# ReducedModel.net
KiCad netlist of a schematic drawn in EAGLE
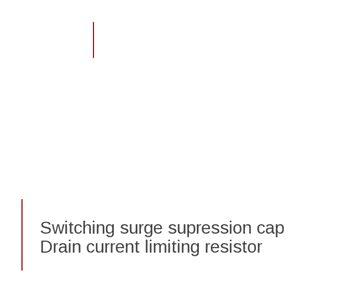
[diagram p0: schematic, sheet 3, part 1 of 2]
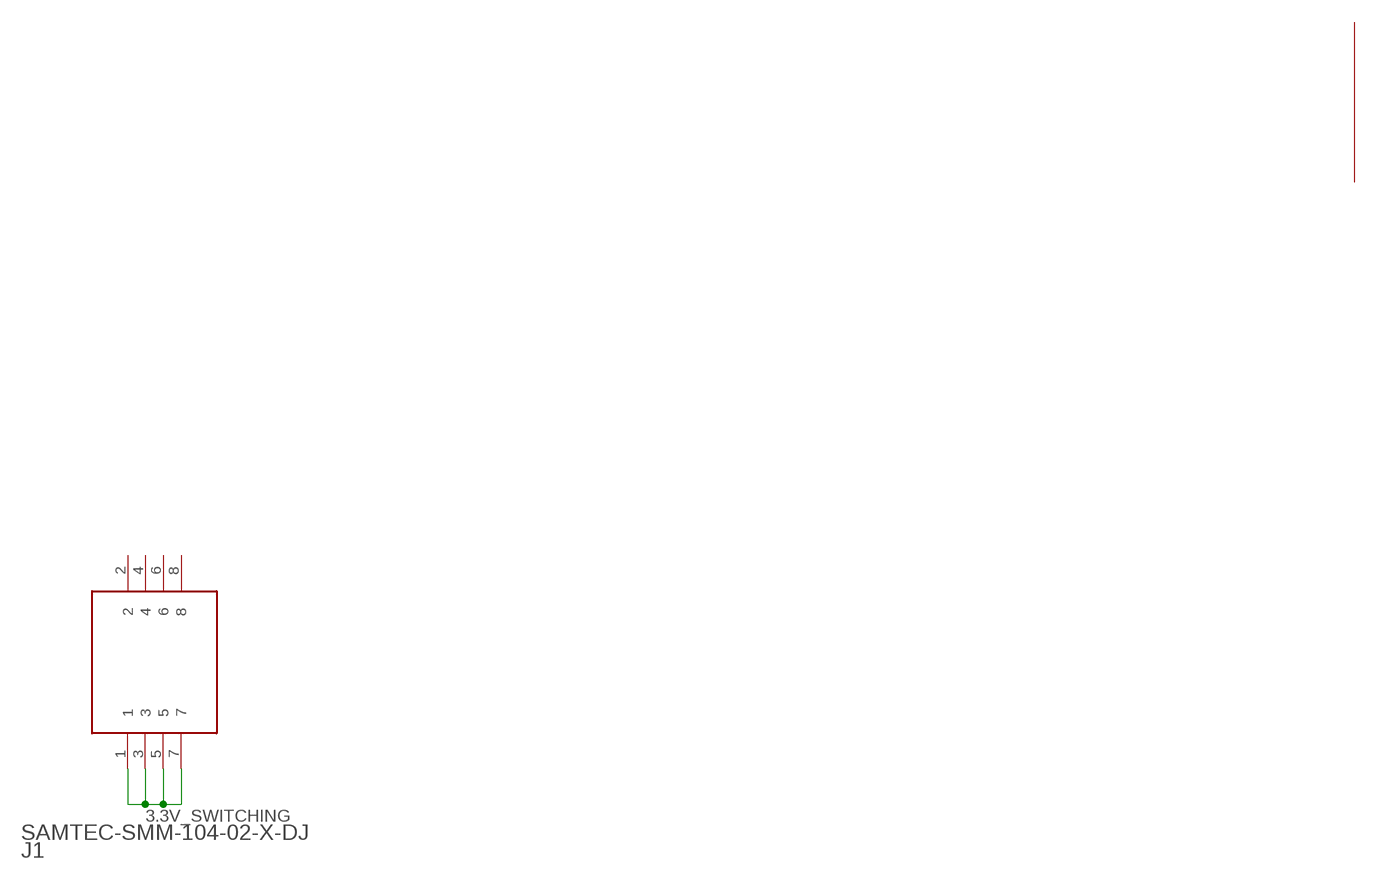
[diagram p1: schematic, sheet 3, part 2 of 2]
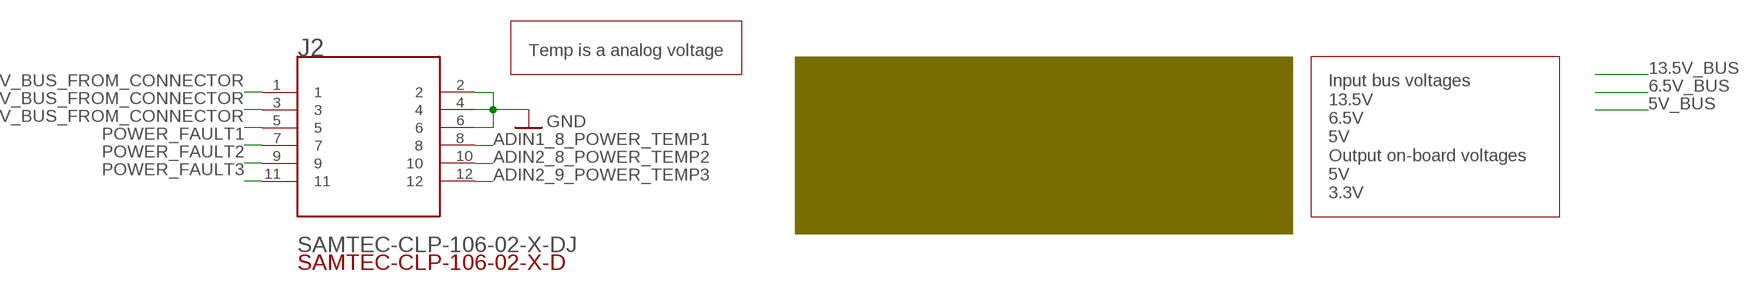
[diagram p2: schematic, sheet 4]
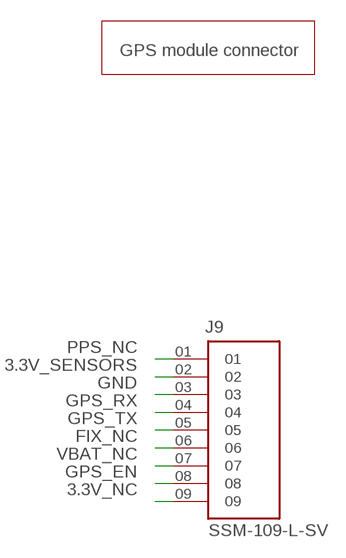
[diagram p3: schematic, sheet 7]
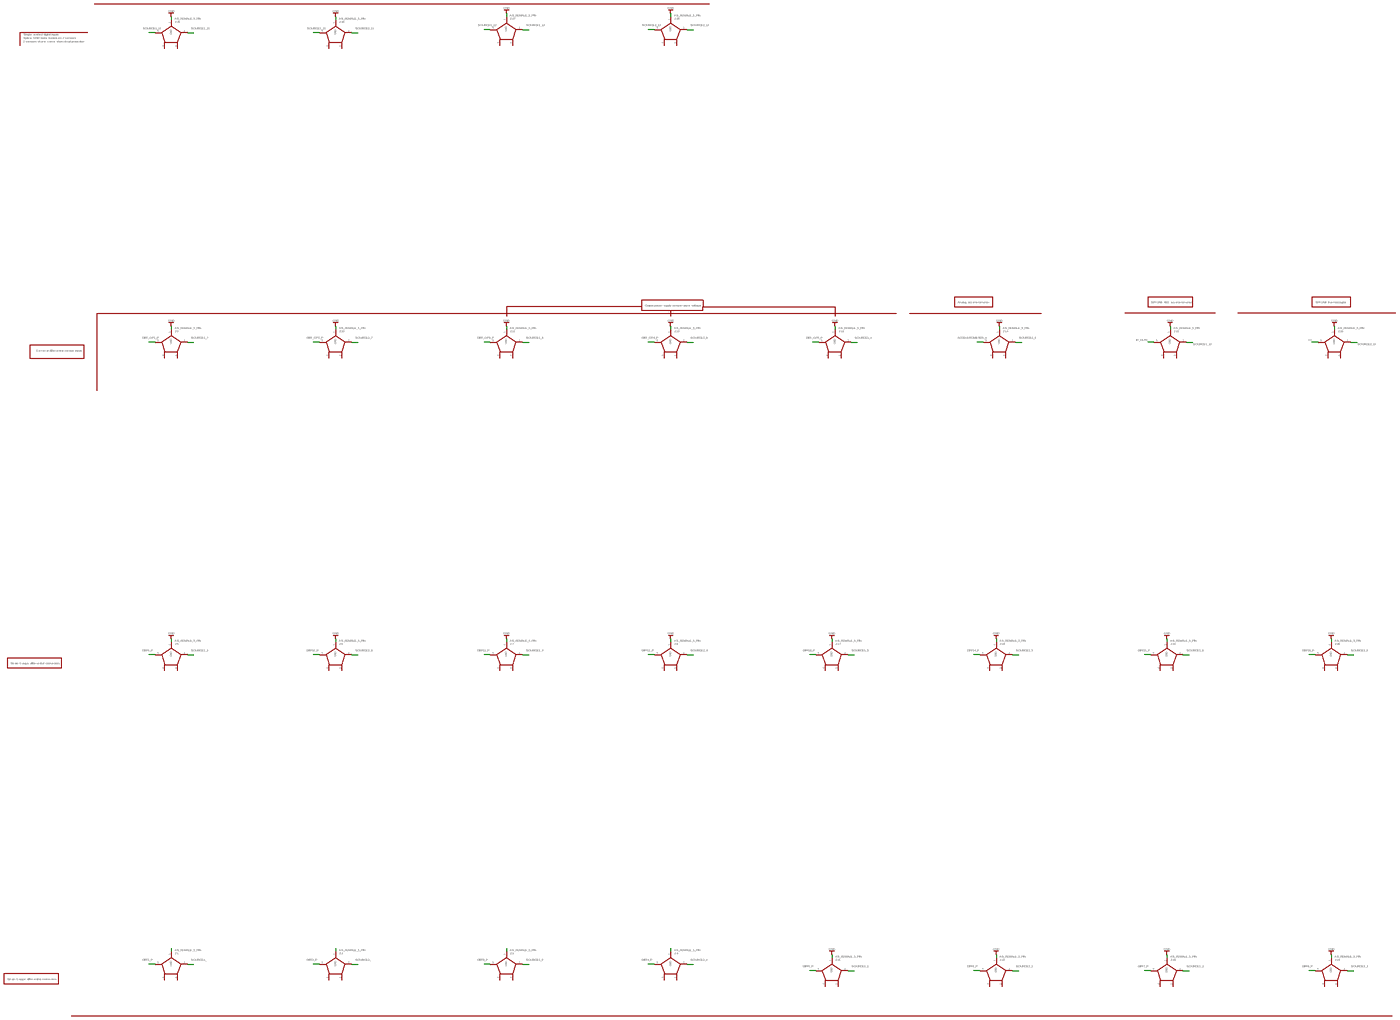
[diagram p4: schematic, sheet 11, overview]
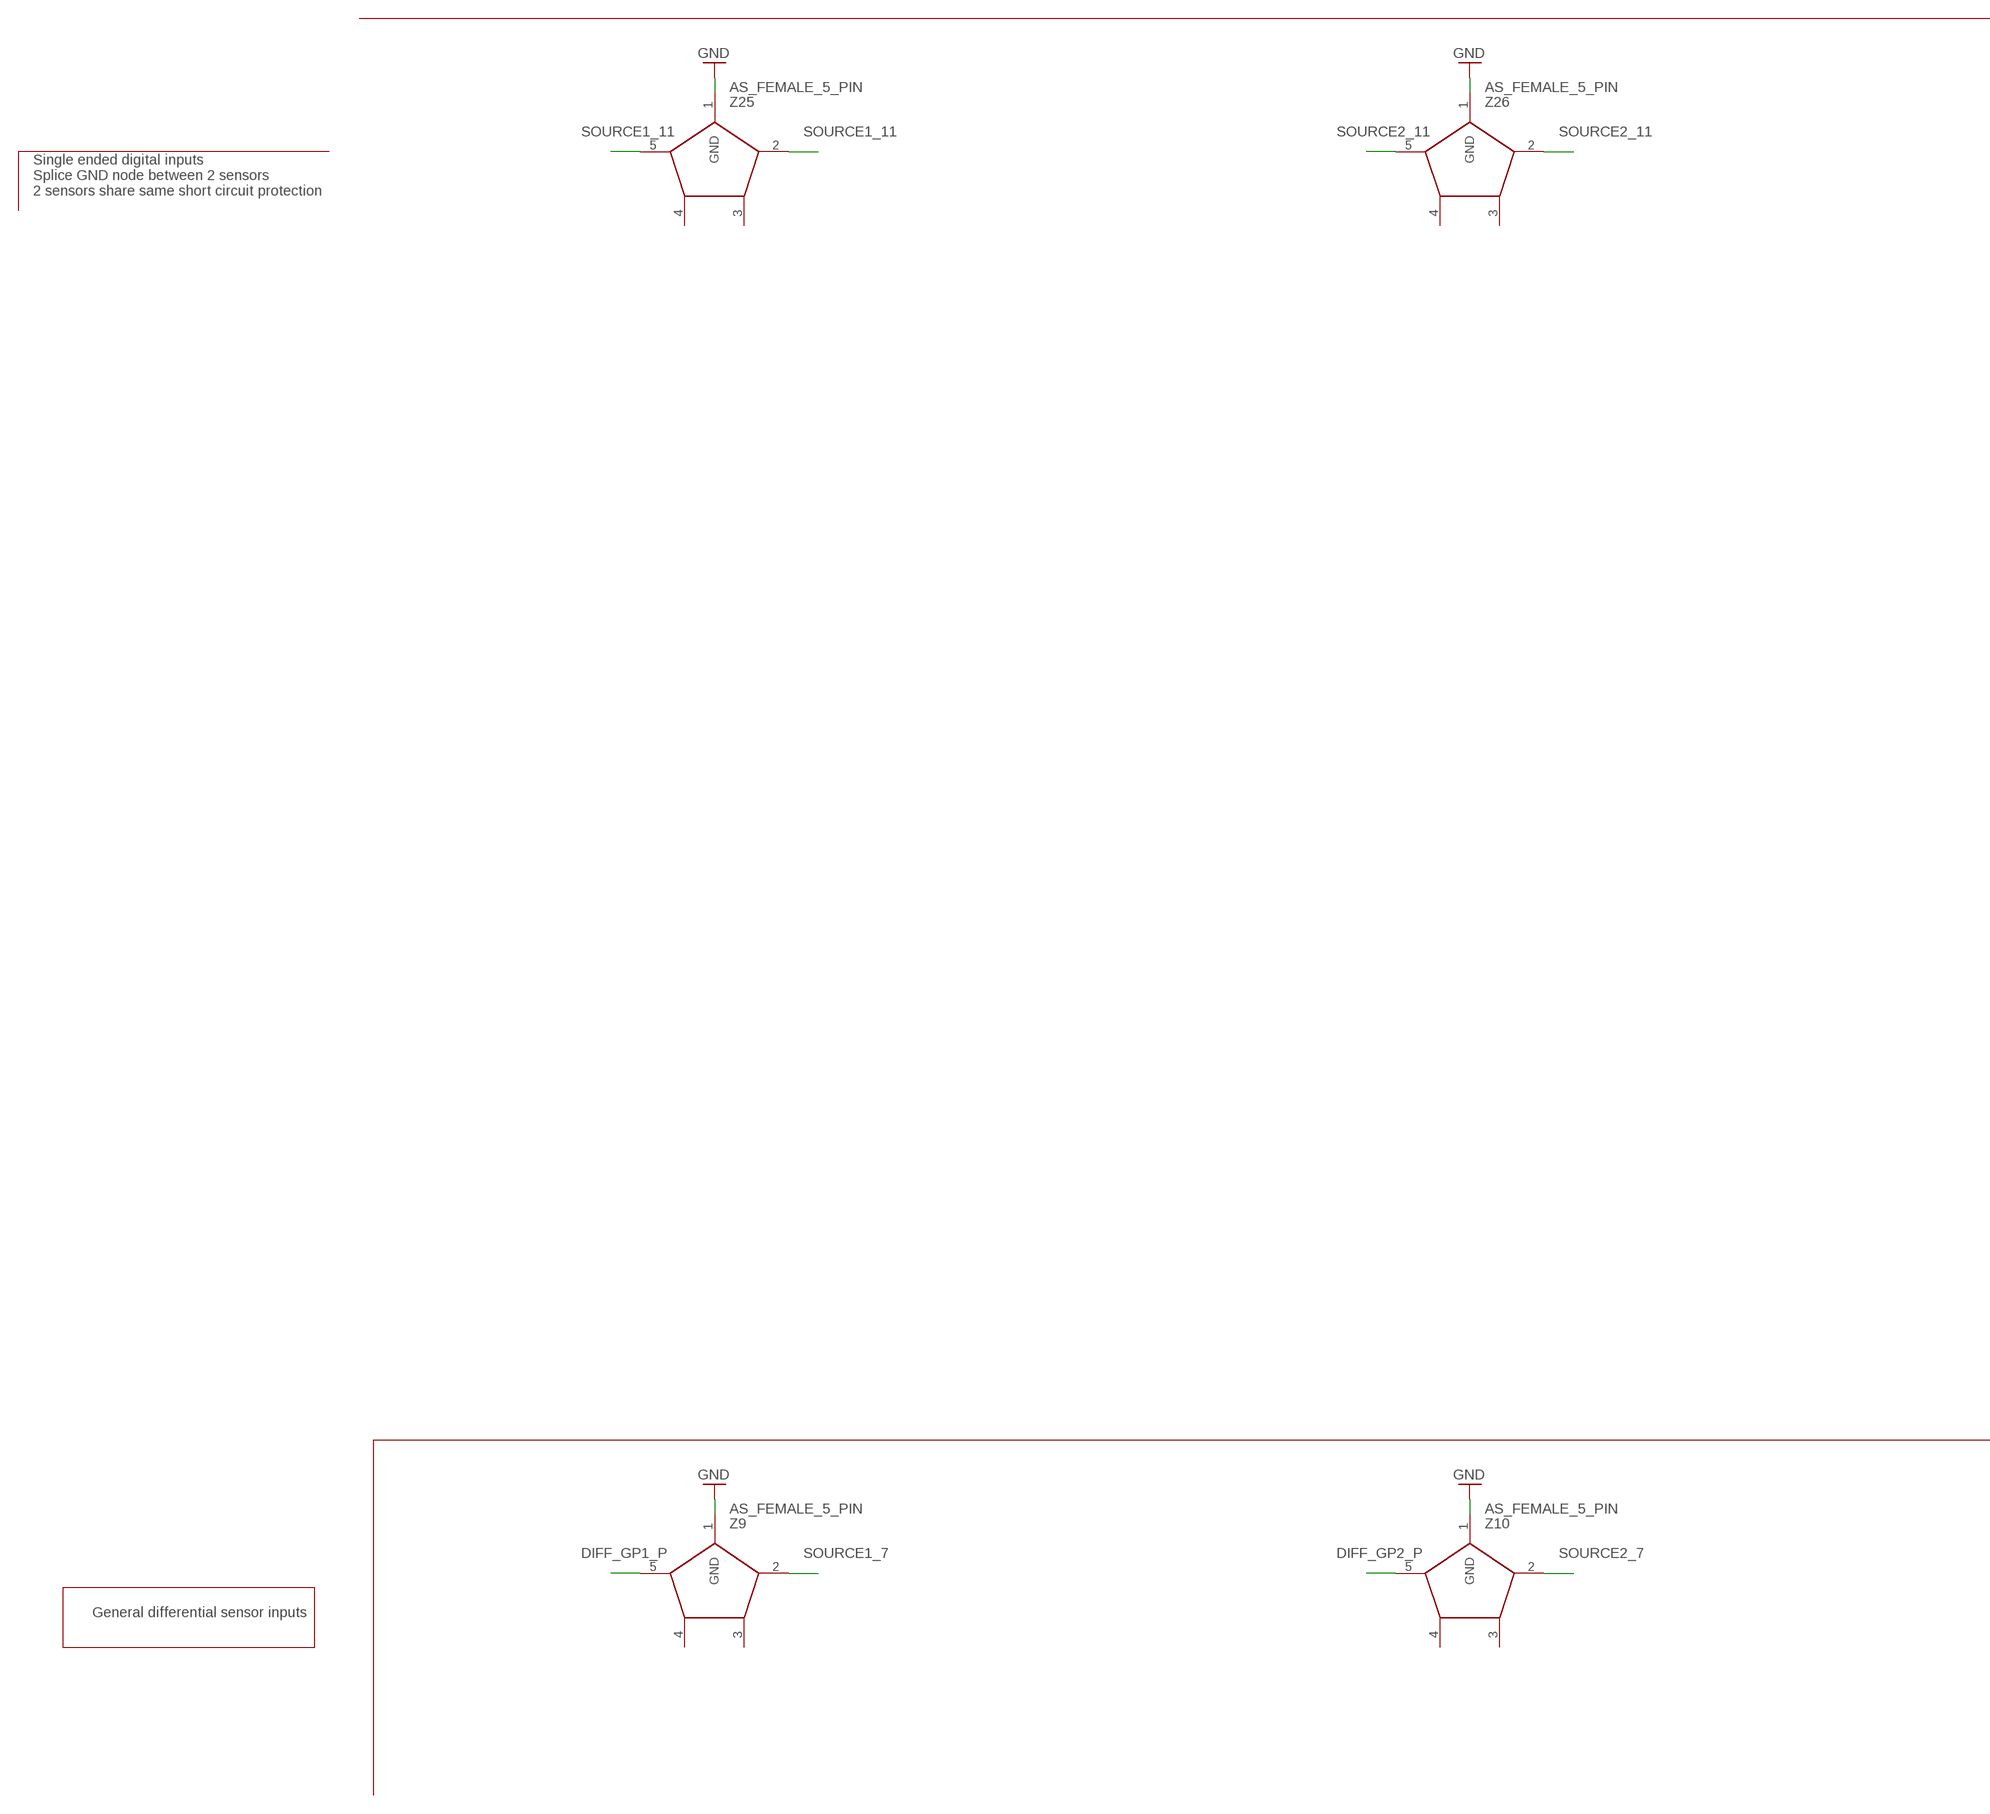
[diagram p5: schematic, sheet 11, part 1 of 6]
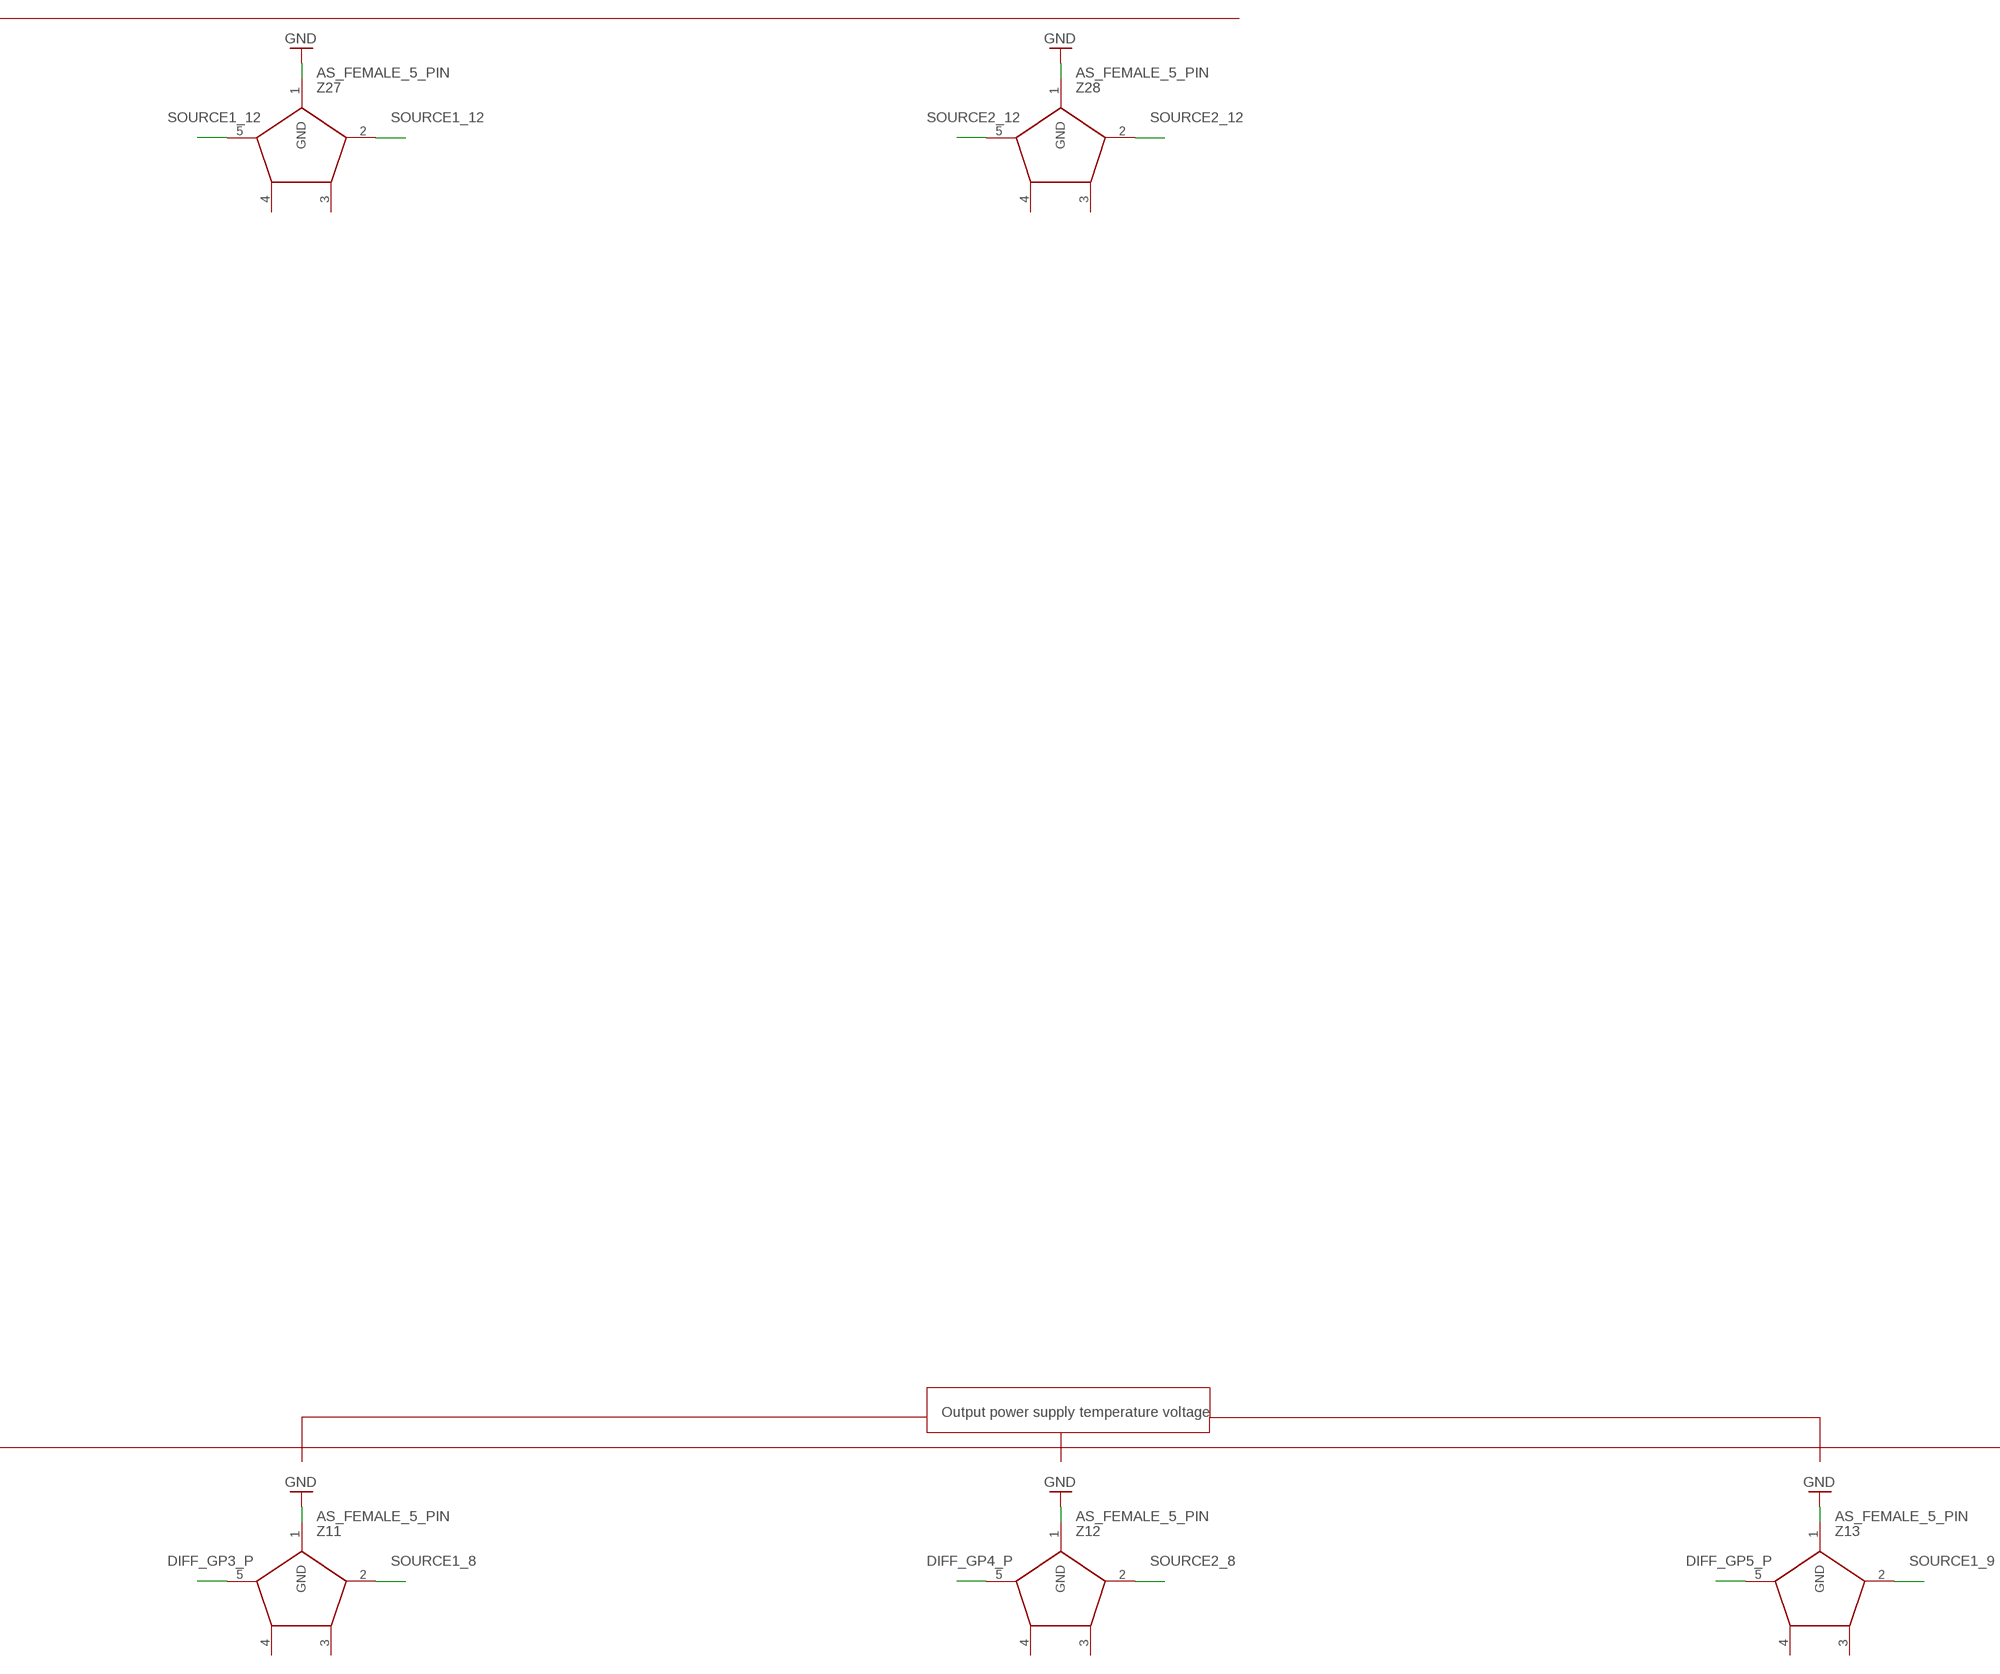
[diagram p6: schematic, sheet 11, part 2 of 6]
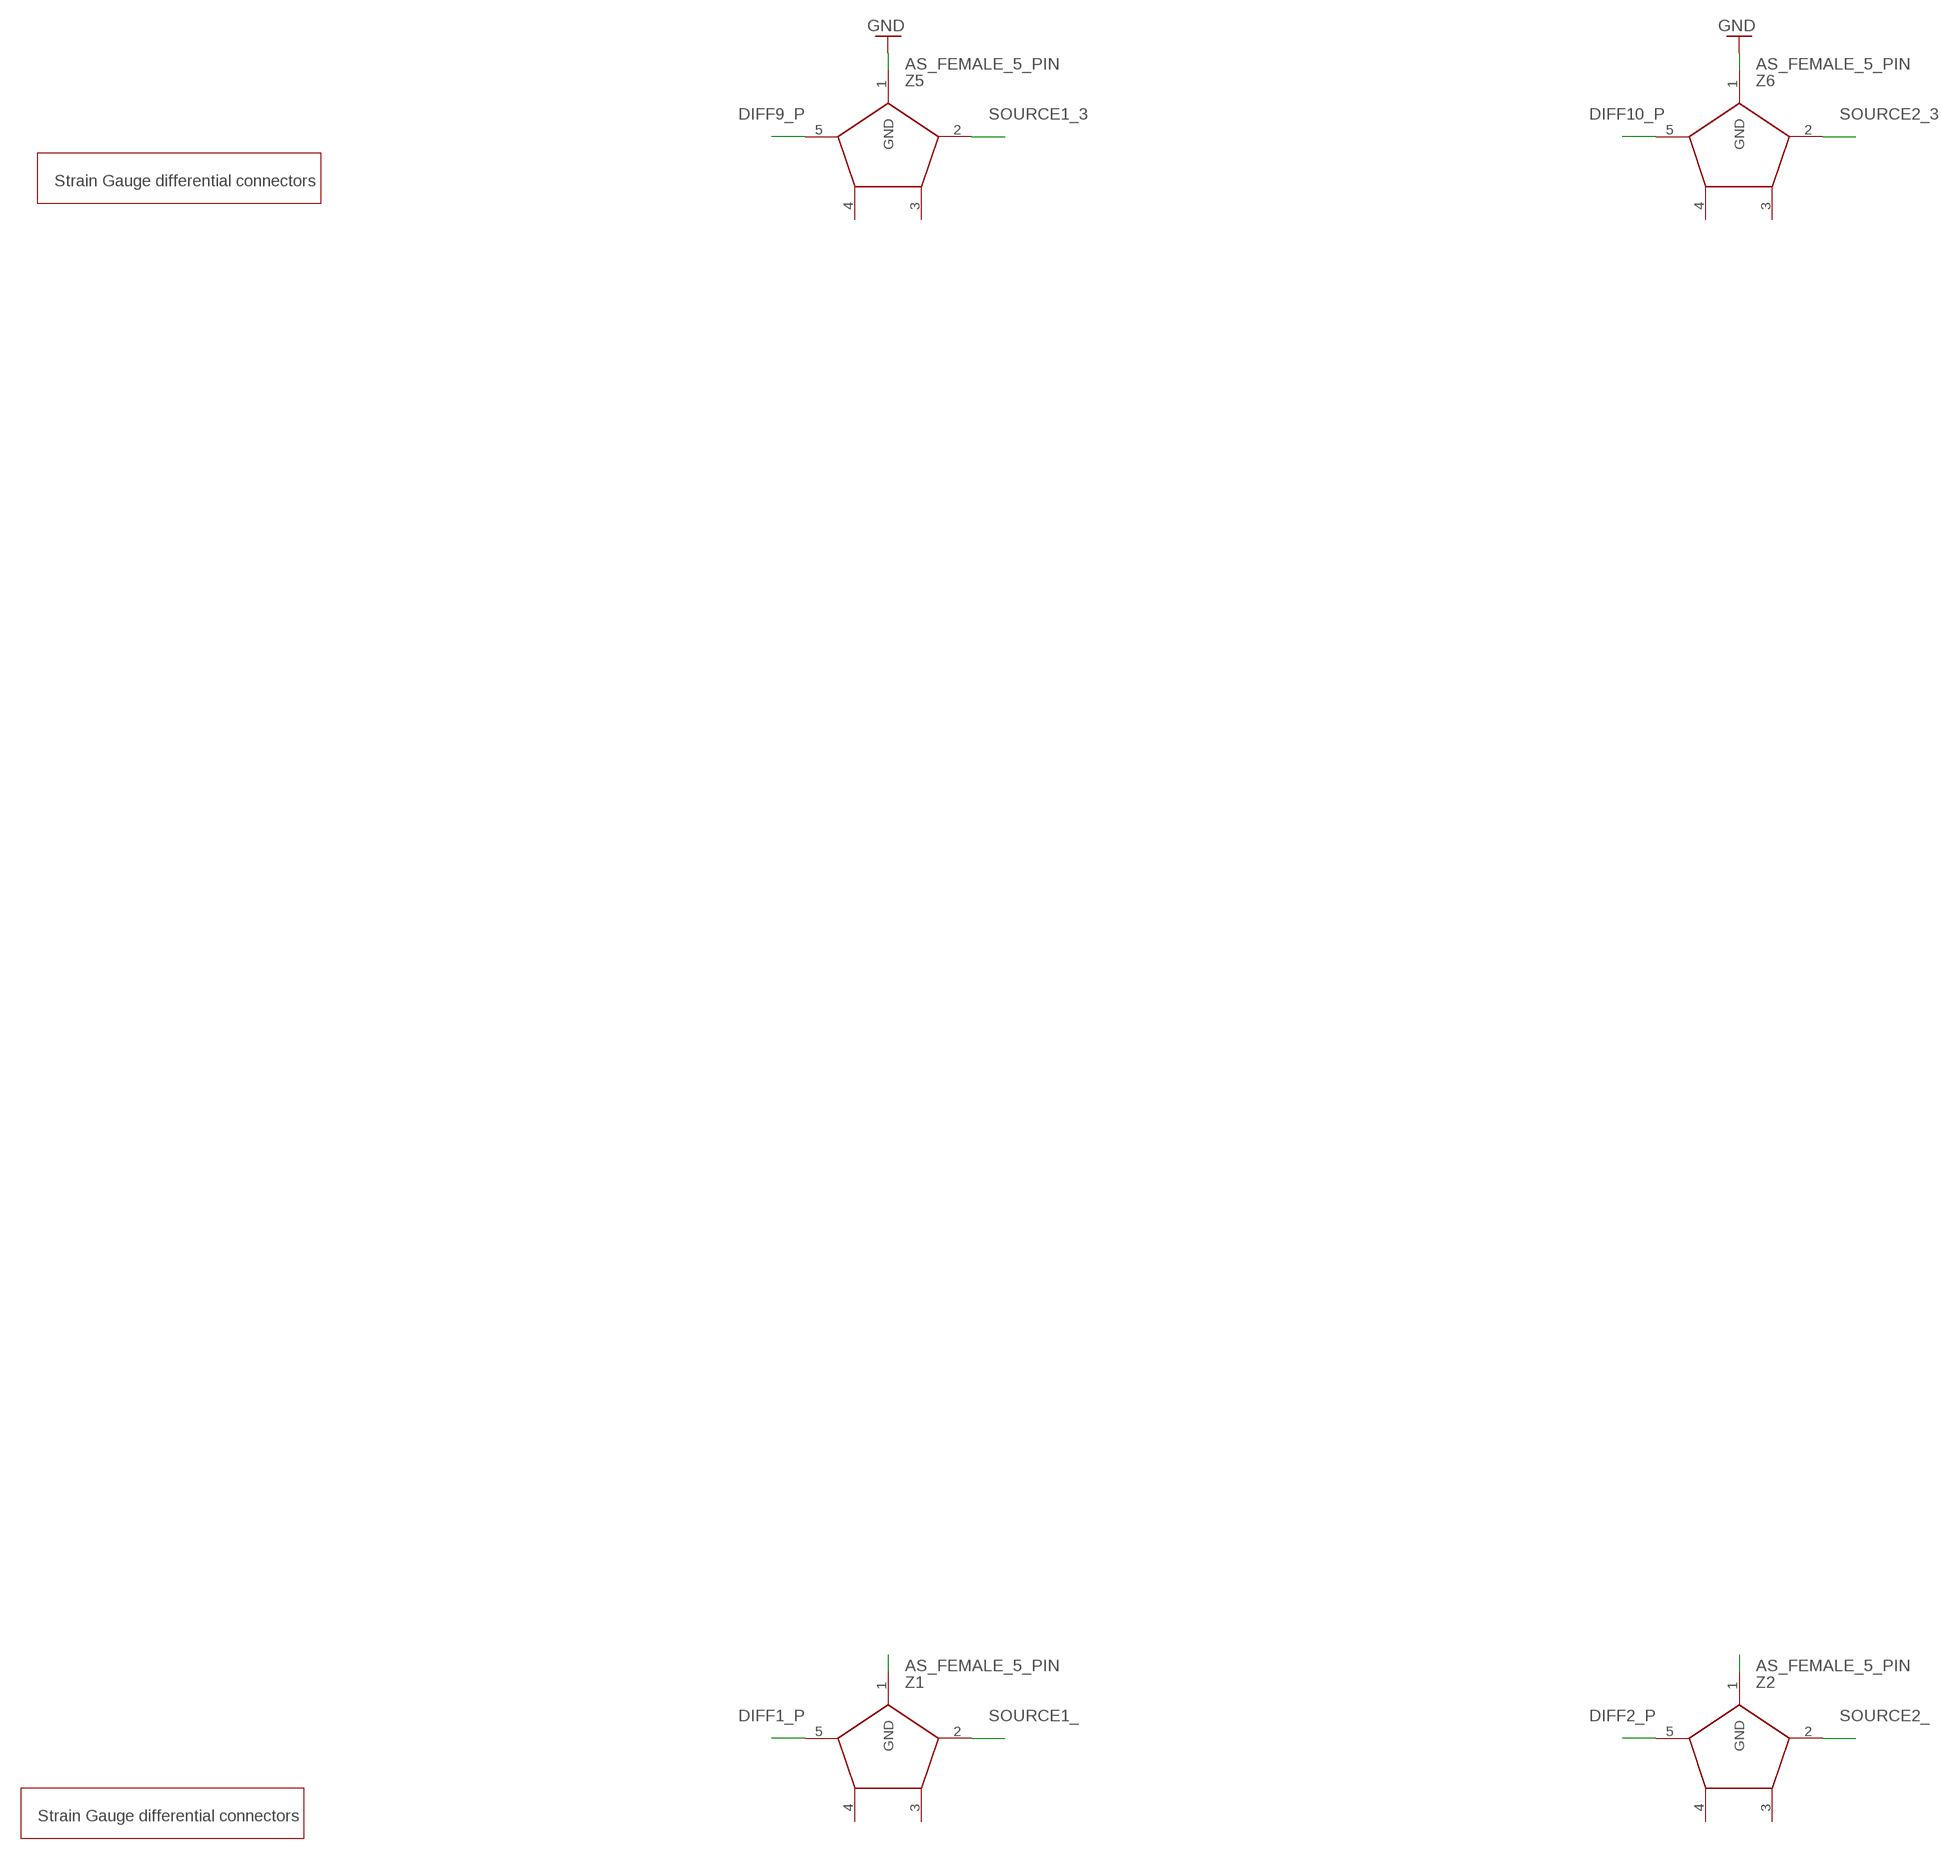
[diagram p7: schematic, sheet 11, part 3 of 6]
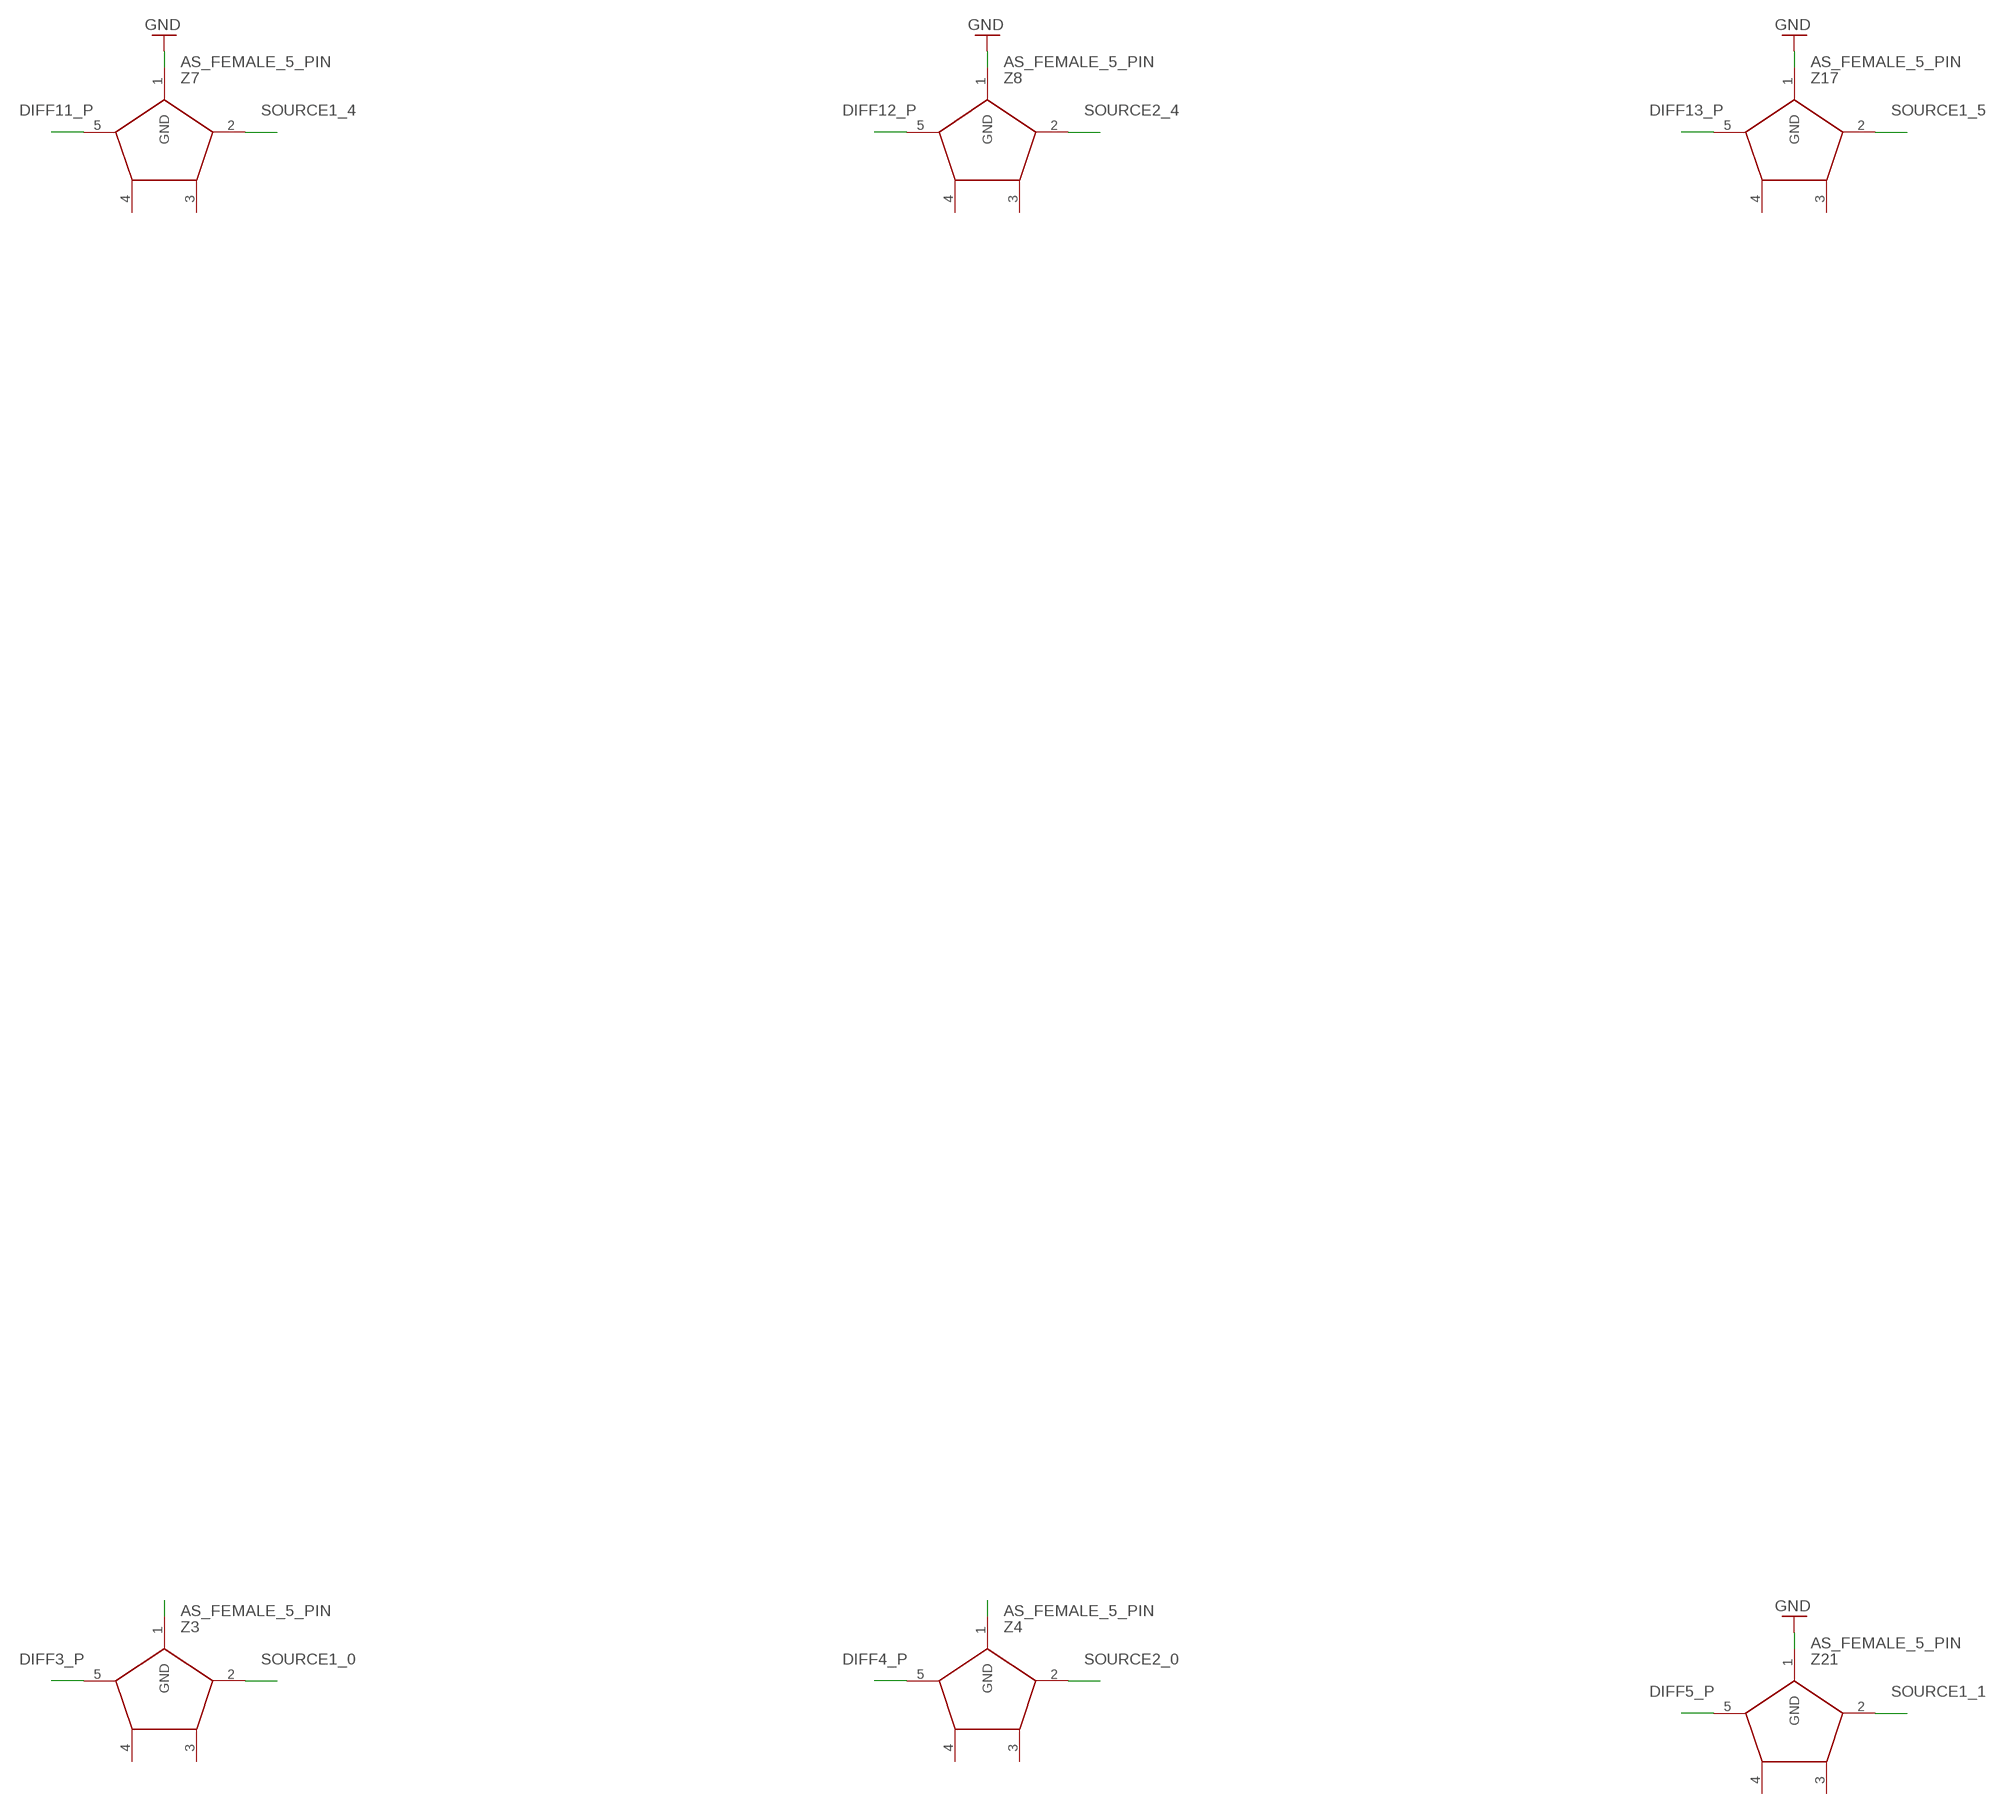
[diagram p8: schematic, sheet 11, part 4 of 6]
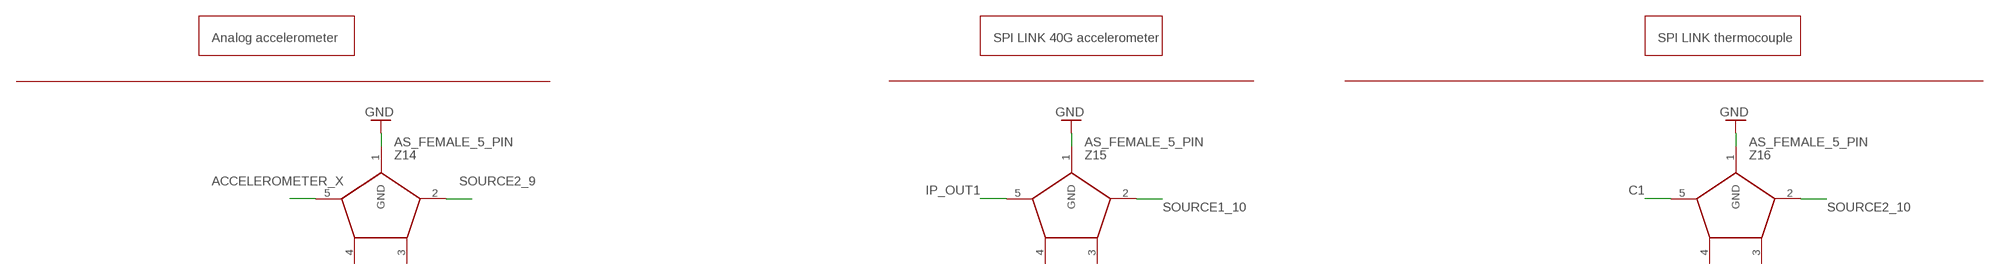
[diagram p9: schematic, sheet 11, part 5 of 6]
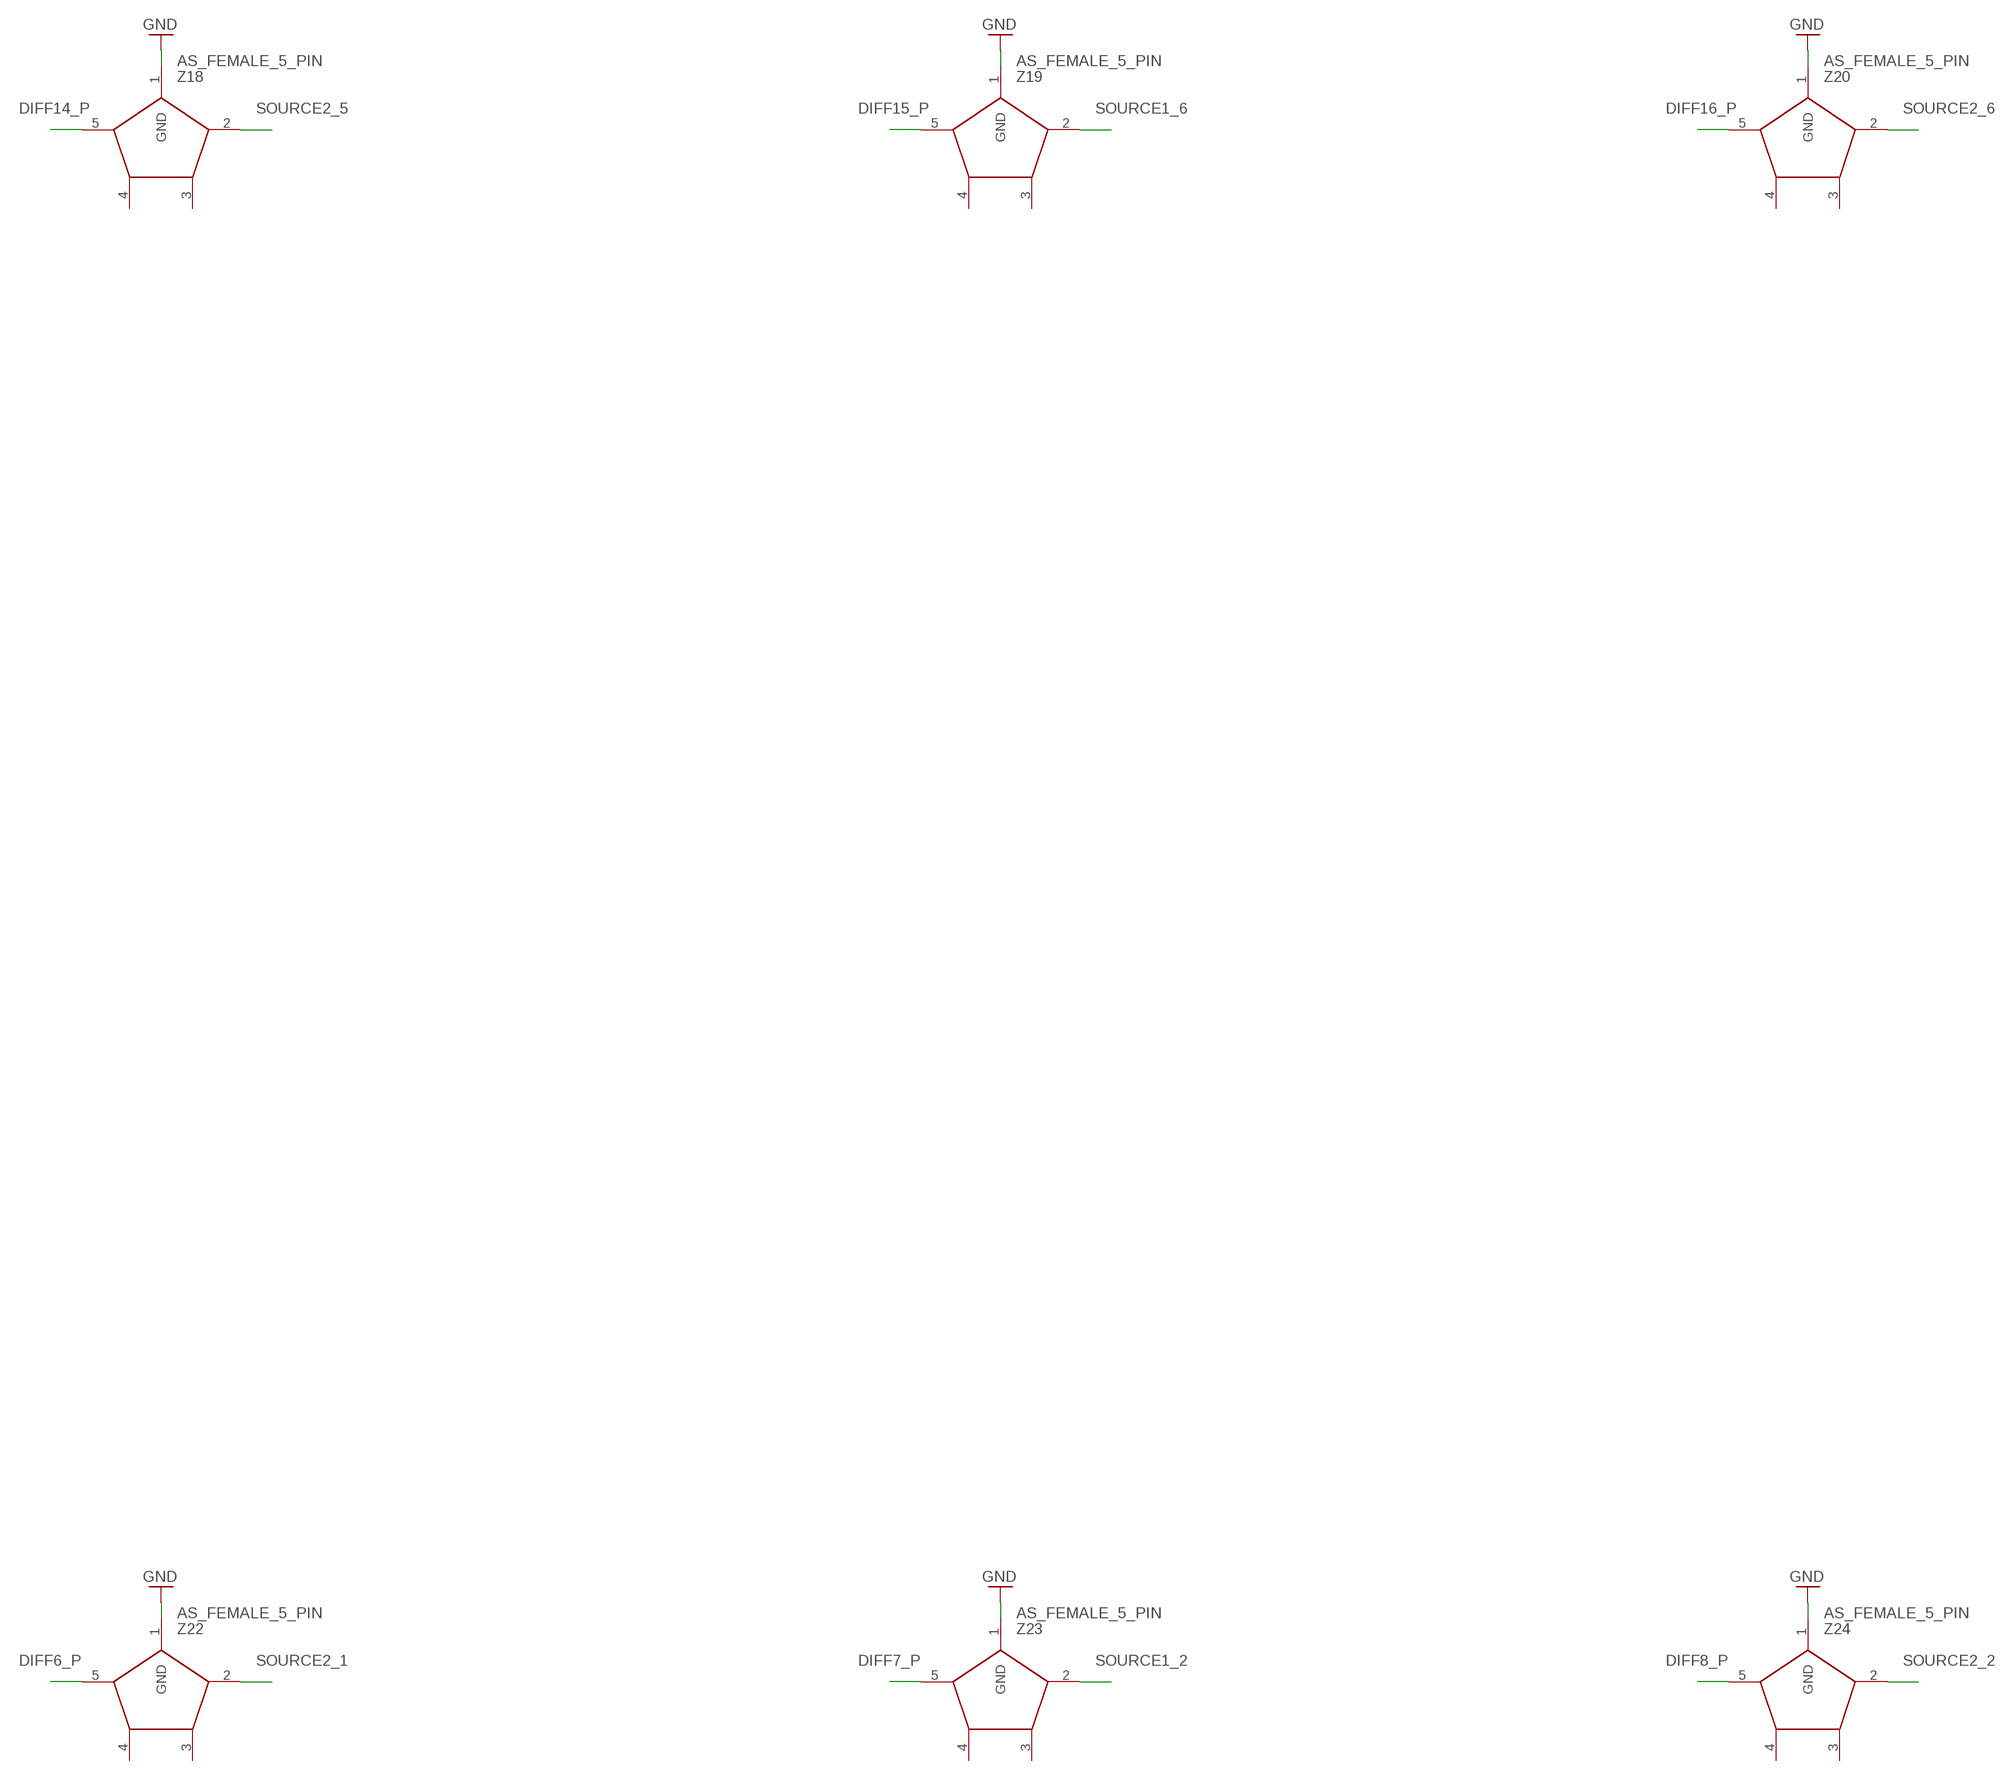
[diagram p10: schematic, sheet 11, part 6 of 6]
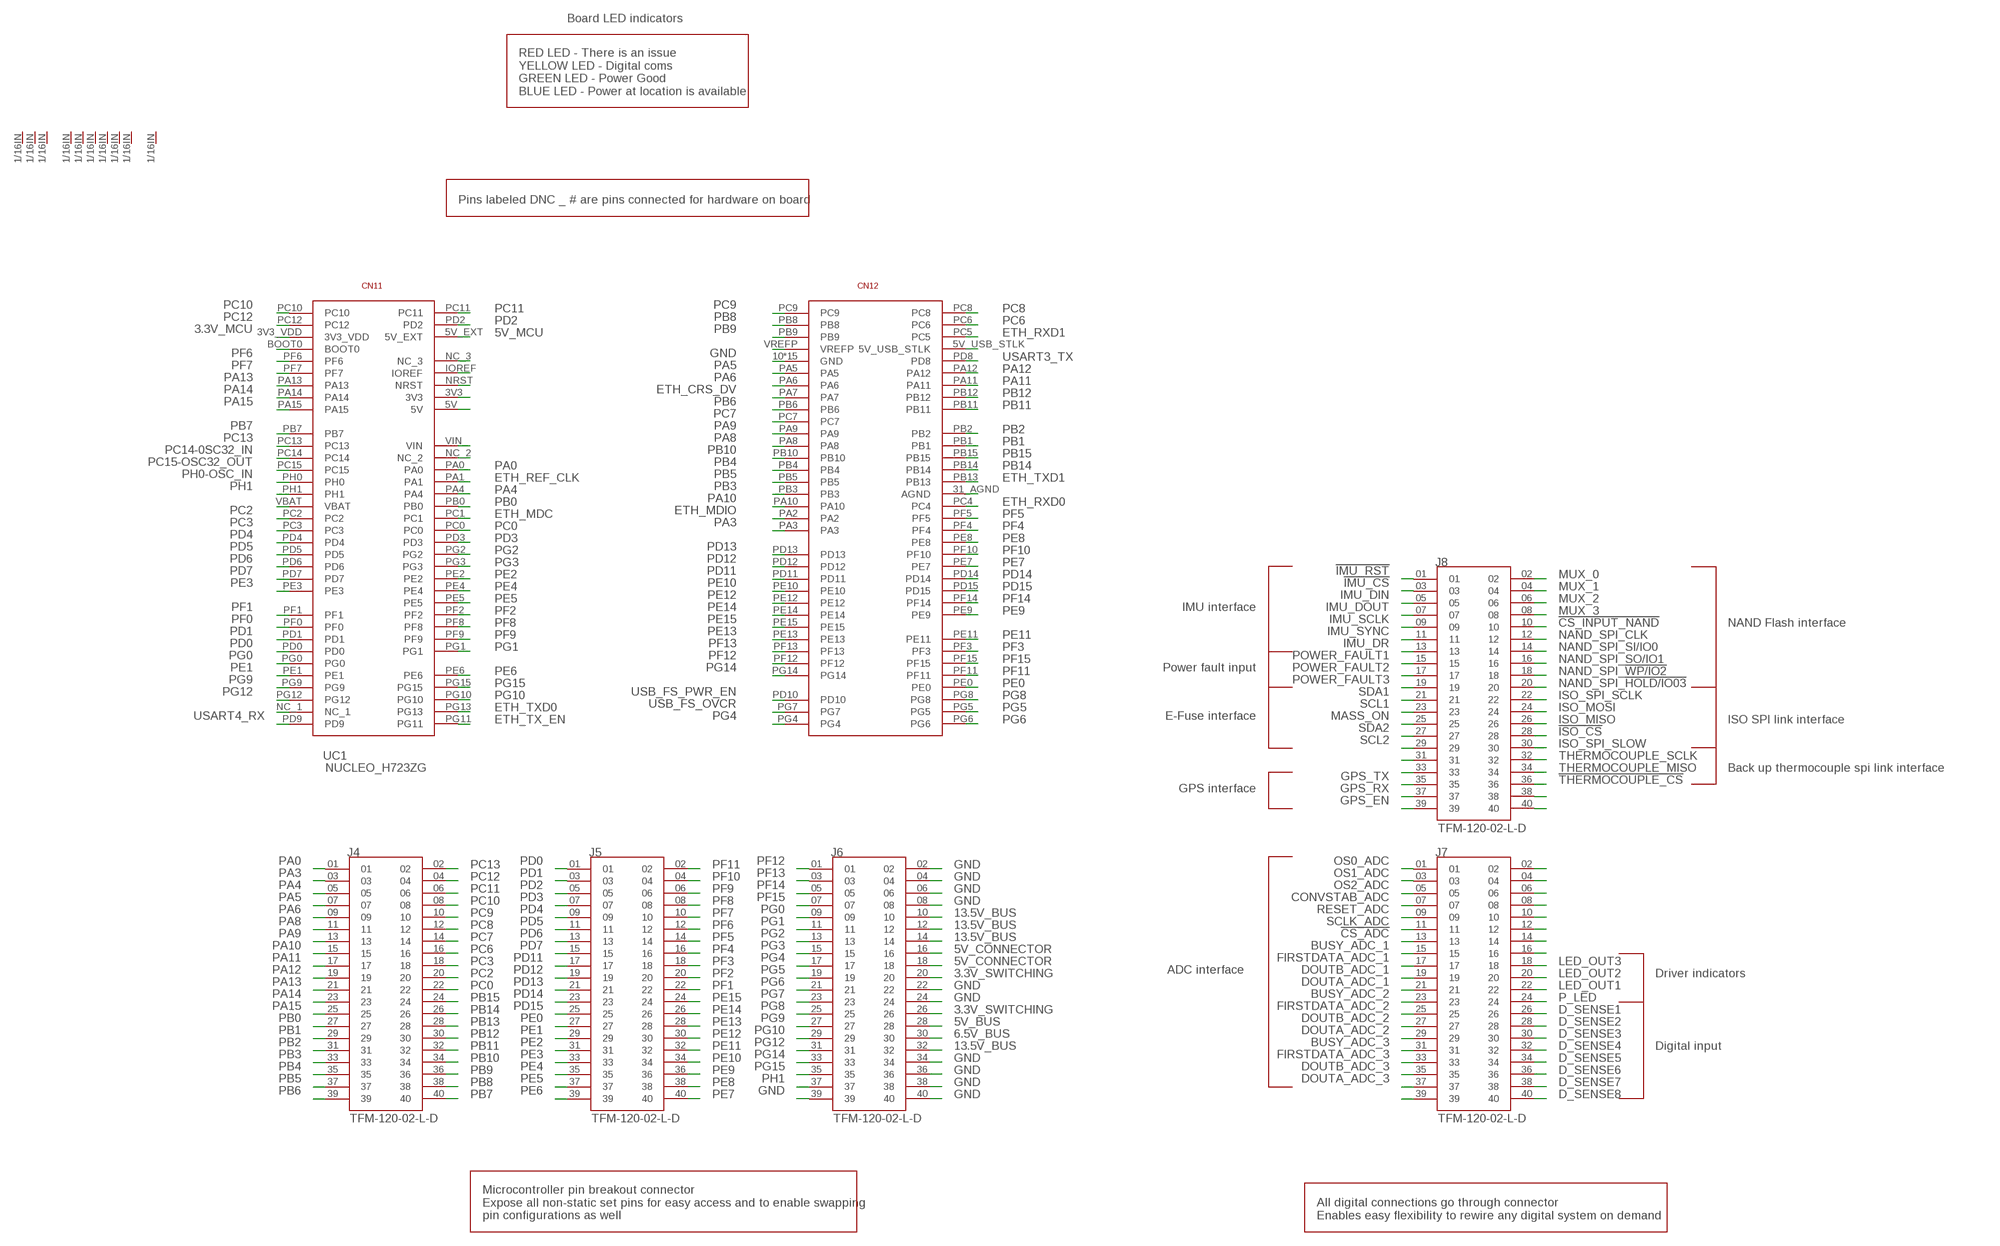
[diagram p11: schematic, sheet 12]

(export (version "E")
  (design (tool "Eeschema 10.0.6"))
  (components
    (comp (ref "J2")
      (value "SAMTEC-CLP-106-02-X-DJ")
      (footprint "eagle-import:SAMTEC-CLP-106-02-X-D")
      (libsource (lib "eagle-import") (part "SAMTEC-CLP-106-02-X-DJ"))
    )
    (comp (ref "J4")
      (value "TFM-120-02-L-D")
      (footprint "eagle-import:SAMTEC_TFM-120-02-L-D")
      (fields (field (name "MANUFACTURER") "Samtec"))
      (libsource (lib "eagle-import") (part "TFM-120-02-L-D"))
    )
    (comp (ref "J5")
      (value "TFM-120-02-L-D")
      (footprint "eagle-import:SAMTEC_TFM-120-02-L-D")
      (fields (field (name "MANUFACTURER") "Samtec"))
      (libsource (lib "eagle-import") (part "TFM-120-02-L-D"))
    )
    (comp (ref "J6")
      (value "TFM-120-02-L-D")
      (footprint "eagle-import:SAMTEC_TFM-120-02-L-D")
      (fields (field (name "MANUFACTURER") "Samtec"))
      (libsource (lib "eagle-import") (part "TFM-120-02-L-D"))
    )
    (comp (ref "J7")
      (value "TFM-120-02-L-D")
      (footprint "eagle-import:SAMTEC_TFM-120-02-L-D")
      (fields (field (name "MANUFACTURER") "Samtec"))
      (libsource (lib "eagle-import") (part "TFM-120-02-L-D"))
    )
    (comp (ref "J8")
      (value "TFM-120-02-L-D")
      (footprint "eagle-import:SAMTEC_TFM-120-02-L-D")
      (fields (field (name "MANUFACTURER") "Samtec"))
      (libsource (lib "eagle-import") (part "TFM-120-02-L-D"))
    )
    (comp (ref "U$5")
      (value "THROUGH_HOLE")
      (footprint "eagle-import:1_16TH_BOLT")
      (libsource (lib "eagle-import") (part "THROUGH_HOLE"))
    )
    (comp (ref "U$6")
      (value "THROUGH_HOLE")
      (footprint "eagle-import:1_16TH_BOLT")
      (libsource (lib "eagle-import") (part "THROUGH_HOLE"))
    )
    (comp (ref "U$7")
      (value "THROUGH_HOLE")
      (footprint "eagle-import:1_16TH_BOLT")
      (libsource (lib "eagle-import") (part "THROUGH_HOLE"))
    )
    (comp (ref "U$8")
      (value "THROUGH_HOLE")
      (footprint "eagle-import:1_16TH_BOLT")
      (libsource (lib "eagle-import") (part "THROUGH_HOLE"))
    )
    (comp (ref "U$9")
      (value "THROUGH_HOLE")
      (footprint "eagle-import:1_16TH_BOLT")
      (libsource (lib "eagle-import") (part "THROUGH_HOLE"))
    )
    (comp (ref "U$10")
      (value "THROUGH_HOLE")
      (footprint "eagle-import:1_16TH_BOLT")
      (libsource (lib "eagle-import") (part "THROUGH_HOLE"))
    )
    (comp (ref "U$12")
      (value "THROUGH_HOLE")
      (footprint "eagle-import:1_16TH_BOLT")
      (libsource (lib "eagle-import") (part "THROUGH_HOLE"))
    )
    (comp (ref "U$13")
      (value "THROUGH_HOLE")
      (footprint "eagle-import:1_16TH_BOLT")
      (libsource (lib "eagle-import") (part "THROUGH_HOLE"))
    )
    (comp (ref "U$14")
      (value "THROUGH_HOLE")
      (footprint "eagle-import:1_16TH_BOLT")
      (libsource (lib "eagle-import") (part "THROUGH_HOLE"))
    )
    (comp (ref "U$15")
      (value "THROUGH_HOLE")
      (footprint "eagle-import:1_16TH_BOLT")
      (libsource (lib "eagle-import") (part "THROUGH_HOLE"))
    )
    (comp (ref "UC1")
      (value "NUCLEO_H723ZG")
      (footprint "eagle-import:NUCLEO_H723ZG")
      (libsource (lib "eagle-import") (part "NUCLEO_H723ZG"))
    )
    (comp (ref "J1")
      (value "SAMTEC-SMM-104-02-X-DJ")
      (footprint "eagle-import:SAMTEC-SMM-104-02-X-D")
      (libsource (lib "eagle-import") (part "SAMTEC-SMM-104-02-X-DJ"))
    )
    (comp (ref "Z1")
      (value "AS_FEMALE_5_PIN")
      (footprint "eagle-import:AS_FEMALE_5_PIN")
      (libsource (lib "eagle-import") (part "AS_FEMALE_5_PIN"))
    )
    (comp (ref "Z2")
      (value "AS_FEMALE_5_PIN")
      (footprint "eagle-import:AS_FEMALE_5_PIN")
      (libsource (lib "eagle-import") (part "AS_FEMALE_5_PIN"))
    )
    (comp (ref "Z3")
      (value "AS_FEMALE_5_PIN")
      (footprint "eagle-import:AS_FEMALE_5_PIN")
      (libsource (lib "eagle-import") (part "AS_FEMALE_5_PIN"))
    )
    (comp (ref "Z4")
      (value "AS_FEMALE_5_PIN")
      (footprint "eagle-import:AS_FEMALE_5_PIN")
      (libsource (lib "eagle-import") (part "AS_FEMALE_5_PIN"))
    )
    (comp (ref "Z5")
      (value "AS_FEMALE_5_PIN")
      (footprint "eagle-import:AS_FEMALE_5_PIN")
      (libsource (lib "eagle-import") (part "AS_FEMALE_5_PIN"))
    )
    (comp (ref "Z6")
      (value "AS_FEMALE_5_PIN")
      (footprint "eagle-import:AS_FEMALE_5_PIN")
      (libsource (lib "eagle-import") (part "AS_FEMALE_5_PIN"))
    )
    (comp (ref "Z7")
      (value "AS_FEMALE_5_PIN")
      (footprint "eagle-import:AS_FEMALE_5_PIN")
      (libsource (lib "eagle-import") (part "AS_FEMALE_5_PIN"))
    )
    (comp (ref "Z8")
      (value "AS_FEMALE_5_PIN")
      (footprint "eagle-import:AS_FEMALE_5_PIN")
      (libsource (lib "eagle-import") (part "AS_FEMALE_5_PIN"))
    )
    (comp (ref "Z9")
      (value "AS_FEMALE_5_PIN")
      (footprint "eagle-import:AS_FEMALE_5_PIN")
      (libsource (lib "eagle-import") (part "AS_FEMALE_5_PIN"))
    )
    (comp (ref "Z10")
      (value "AS_FEMALE_5_PIN")
      (footprint "eagle-import:AS_FEMALE_5_PIN")
      (libsource (lib "eagle-import") (part "AS_FEMALE_5_PIN"))
    )
    (comp (ref "Z11")
      (value "AS_FEMALE_5_PIN")
      (footprint "eagle-import:AS_FEMALE_5_PIN")
      (libsource (lib "eagle-import") (part "AS_FEMALE_5_PIN"))
    )
    (comp (ref "Z12")
      (value "AS_FEMALE_5_PIN")
      (footprint "eagle-import:AS_FEMALE_5_PIN")
      (libsource (lib "eagle-import") (part "AS_FEMALE_5_PIN"))
    )
    (comp (ref "Z13")
      (value "AS_FEMALE_5_PIN")
      (footprint "eagle-import:AS_FEMALE_5_PIN")
      (libsource (lib "eagle-import") (part "AS_FEMALE_5_PIN"))
    )
    (comp (ref "Z14")
      (value "AS_FEMALE_5_PIN")
      (footprint "eagle-import:AS_FEMALE_5_PIN")
      (libsource (lib "eagle-import") (part "AS_FEMALE_5_PIN"))
    )
    (comp (ref "Z15")
      (value "AS_FEMALE_5_PIN")
      (footprint "eagle-import:AS_FEMALE_5_PIN")
      (libsource (lib "eagle-import") (part "AS_FEMALE_5_PIN"))
    )
    (comp (ref "Z16")
      (value "AS_FEMALE_5_PIN")
      (footprint "eagle-import:AS_FEMALE_5_PIN")
      (libsource (lib "eagle-import") (part "AS_FEMALE_5_PIN"))
    )
    (comp (ref "Z17")
      (value "AS_FEMALE_5_PIN")
      (footprint "eagle-import:AS_FEMALE_5_PIN")
      (libsource (lib "eagle-import") (part "AS_FEMALE_5_PIN"))
    )
    (comp (ref "Z18")
      (value "AS_FEMALE_5_PIN")
      (footprint "eagle-import:AS_FEMALE_5_PIN")
      (libsource (lib "eagle-import") (part "AS_FEMALE_5_PIN"))
    )
    (comp (ref "Z19")
      (value "AS_FEMALE_5_PIN")
      (footprint "eagle-import:AS_FEMALE_5_PIN")
      (libsource (lib "eagle-import") (part "AS_FEMALE_5_PIN"))
    )
    (comp (ref "Z20")
      (value "AS_FEMALE_5_PIN")
      (footprint "eagle-import:AS_FEMALE_5_PIN")
      (libsource (lib "eagle-import") (part "AS_FEMALE_5_PIN"))
    )
    (comp (ref "Z21")
      (value "AS_FEMALE_5_PIN")
      (footprint "eagle-import:AS_FEMALE_5_PIN")
      (libsource (lib "eagle-import") (part "AS_FEMALE_5_PIN"))
    )
    (comp (ref "Z22")
      (value "AS_FEMALE_5_PIN")
      (footprint "eagle-import:AS_FEMALE_5_PIN")
      (libsource (lib "eagle-import") (part "AS_FEMALE_5_PIN"))
    )
    (comp (ref "Z23")
      (value "AS_FEMALE_5_PIN")
      (footprint "eagle-import:AS_FEMALE_5_PIN")
      (libsource (lib "eagle-import") (part "AS_FEMALE_5_PIN"))
    )
    (comp (ref "Z24")
      (value "AS_FEMALE_5_PIN")
      (footprint "eagle-import:AS_FEMALE_5_PIN")
      (libsource (lib "eagle-import") (part "AS_FEMALE_5_PIN"))
    )
    (comp (ref "Z25")
      (value "AS_FEMALE_5_PIN")
      (footprint "eagle-import:AS_FEMALE_5_PIN")
      (libsource (lib "eagle-import") (part "AS_FEMALE_5_PIN"))
    )
    (comp (ref "Z26")
      (value "AS_FEMALE_5_PIN")
      (footprint "eagle-import:AS_FEMALE_5_PIN")
      (libsource (lib "eagle-import") (part "AS_FEMALE_5_PIN"))
    )
    (comp (ref "Z27")
      (value "AS_FEMALE_5_PIN")
      (footprint "eagle-import:AS_FEMALE_5_PIN")
      (libsource (lib "eagle-import") (part "AS_FEMALE_5_PIN"))
    )
    (comp (ref "Z28")
      (value "AS_FEMALE_5_PIN")
      (footprint "eagle-import:AS_FEMALE_5_PIN")
      (libsource (lib "eagle-import") (part "AS_FEMALE_5_PIN"))
    )
    (comp (ref "J9")
      (value "SSM-109-L-SV")
      (footprint "eagle-import:SAMTEC_SSM-109-L-SV")
      (fields (field (name "MANUFACTURER") "SAMTEC "))
      (libsource (lib "eagle-import") (part "SSM-109-L-SV"))
    )
  )
  (nets
    (net (code "1") (name "3.3V_MCU") (class "Default")
      (node (ref "UC1") (pin "3V3_VDD") (pinfunction "3V3_VDD_3V3_VDD") (pintype "passive"))
    )
    (net (code "2") (name "3.3V_NC") (class "Default")
      (node (ref "J9") (pin "09") (pinfunction "09_09") (pintype "passive"))
    )
    (net (code "3") (name "3.3V_SENSORS") (class "Default")
      (node (ref "J9") (pin "02") (pinfunction "02_02") (pintype "passive"))
    )
    (net (code "4") (name "3.3V_SWITCHING") (class "Default")
      (node (ref "J1") (pin "1") (pinfunction "1_1") (pintype "passive"))
      (node (ref "J1") (pin "3") (pinfunction "3_3") (pintype "passive"))
      (node (ref "J1") (pin "5") (pinfunction "5_5") (pintype "passive"))
      (node (ref "J1") (pin "7") (pinfunction "7_7") (pintype "passive"))
      (node (ref "J6") (pin "20") (pinfunction "20_20") (pintype "passive"))
      (node (ref "J6") (pin "26") (pinfunction "26_26") (pintype "passive"))
    )
    (net (code "5") (name "5V_BUS") (class "Default")
      (node (ref "J6") (pin "28") (pinfunction "28_28") (pintype "passive"))
    )
    (net (code "6") (name "5V_BUS_FROM_CONNECTOR") (class "Default")
      (node (ref "J2") (pin "5") (pinfunction "5_5") (pintype "passive"))
    )
    (net (code "7") (name "5V_CONNECTOR") (class "Default")
      (node (ref "J6") (pin "16") (pinfunction "16_16") (pintype "passive"))
      (node (ref "J6") (pin "18") (pinfunction "18_18") (pintype "passive"))
    )
    (net (code "8") (name "5V_MCU") (class "Default")
      (node (ref "UC1") (pin "5V_EXT") (pinfunction "5V_EXT_5V_EXT") (pintype "passive"))
    )
    (net (code "9") (name "6.5V_BUS") (class "Default")
      (node (ref "J6") (pin "30") (pinfunction "30_30") (pintype "passive"))
    )
    (net (code "10") (name "6.5V_BUS_FROM_CONNECTOR") (class "Default")
      (node (ref "J2") (pin "3") (pinfunction "3_3") (pintype "passive"))
    )
    (net (code "11") (name "13.5V_BUS") (class "Default")
      (node (ref "J6") (pin "10") (pinfunction "10_10") (pintype "passive"))
      (node (ref "J6") (pin "12") (pinfunction "12_12") (pintype "passive"))
      (node (ref "J6") (pin "14") (pinfunction "14_14") (pintype "passive"))
      (node (ref "J6") (pin "32") (pinfunction "32_32") (pintype "passive"))
    )
    (net (code "12") (name "14V_BUS_FROM_CONNECTOR") (class "Default")
      (node (ref "J2") (pin "1") (pinfunction "1_1") (pintype "passive"))
    )
    (net (code "13") (name "ACCELEROMETER_X") (class "Default")
      (node (ref "Z14") (pin "5") (pinfunction "4_5") (pintype "bidirectional"))
    )
    (net (code "14") (name "ADIN1_8_POWER_TEMP1") (class "Default")
      (node (ref "J2") (pin "8") (pinfunction "8_8") (pintype "passive"))
    )
    (net (code "15") (name "ADIN2_8_POWER_TEMP2") (class "Default")
      (node (ref "J2") (pin "10") (pinfunction "10_10") (pintype "passive"))
    )
    (net (code "16") (name "ADIN2_9_POWER_TEMP3") (class "Default")
      (node (ref "J2") (pin "12") (pinfunction "12_12") (pintype "passive"))
    )
    (net (code "17") (name "BUSY_ADC_1") (class "Default")
      (node (ref "J7") (pin "15") (pinfunction "15_15") (pintype "passive"))
    )
    (net (code "18") (name "BUSY_ADC_2") (class "Default")
      (node (ref "J7") (pin "23") (pinfunction "23_23") (pintype "passive"))
    )
    (net (code "19") (name "BUSY_ADC_3") (class "Default")
      (node (ref "J7") (pin "31") (pinfunction "31_31") (pintype "passive"))
    )
    (net (code "20") (name "C1") (class "Default")
      (node (ref "Z16") (pin "5") (pinfunction "4_5") (pintype "bidirectional"))
    )
    (net (code "21") (name "CONVSTAB_ADC") (class "Default")
      (node (ref "J7") (pin "07") (pinfunction "07_07") (pintype "passive"))
    )
    (net (code "22") (name "DIFF1_P") (class "Default")
      (node (ref "Z1") (pin "5") (pinfunction "4_5") (pintype "bidirectional"))
    )
    (net (code "23") (name "DIFF2_P") (class "Default")
      (node (ref "Z2") (pin "5") (pinfunction "4_5") (pintype "bidirectional"))
    )
    (net (code "24") (name "DIFF3_P") (class "Default")
      (node (ref "Z3") (pin "5") (pinfunction "4_5") (pintype "bidirectional"))
    )
    (net (code "25") (name "DIFF4_P") (class "Default")
      (node (ref "Z4") (pin "5") (pinfunction "4_5") (pintype "bidirectional"))
    )
    (net (code "26") (name "DIFF5_P") (class "Default")
      (node (ref "Z21") (pin "5") (pinfunction "4_5") (pintype "bidirectional"))
    )
    (net (code "27") (name "DIFF6_P") (class "Default")
      (node (ref "Z22") (pin "5") (pinfunction "4_5") (pintype "bidirectional"))
    )
    (net (code "28") (name "DIFF7_P") (class "Default")
      (node (ref "Z23") (pin "5") (pinfunction "4_5") (pintype "bidirectional"))
    )
    (net (code "29") (name "DIFF8_P") (class "Default")
      (node (ref "Z24") (pin "5") (pinfunction "4_5") (pintype "bidirectional"))
    )
    (net (code "30") (name "DIFF9_P") (class "Default")
      (node (ref "Z5") (pin "5") (pinfunction "4_5") (pintype "bidirectional"))
    )
    (net (code "31") (name "DIFF10_P") (class "Default")
      (node (ref "Z6") (pin "5") (pinfunction "4_5") (pintype "bidirectional"))
    )
    (net (code "32") (name "DIFF11_P") (class "Default")
      (node (ref "Z7") (pin "5") (pinfunction "4_5") (pintype "bidirectional"))
    )
    (net (code "33") (name "DIFF12_P") (class "Default")
      (node (ref "Z8") (pin "5") (pinfunction "4_5") (pintype "bidirectional"))
    )
    (net (code "34") (name "DIFF13_P") (class "Default")
      (node (ref "Z17") (pin "5") (pinfunction "4_5") (pintype "bidirectional"))
    )
    (net (code "35") (name "DIFF14_P") (class "Default")
      (node (ref "Z18") (pin "5") (pinfunction "4_5") (pintype "bidirectional"))
    )
    (net (code "36") (name "DIFF15_P") (class "Default")
      (node (ref "Z19") (pin "5") (pinfunction "4_5") (pintype "bidirectional"))
    )
    (net (code "37") (name "DIFF16_P") (class "Default")
      (node (ref "Z20") (pin "5") (pinfunction "4_5") (pintype "bidirectional"))
    )
    (net (code "38") (name "DIFF_GP1_P") (class "Default")
      (node (ref "Z9") (pin "5") (pinfunction "4_5") (pintype "bidirectional"))
    )
    (net (code "39") (name "DIFF_GP2_P") (class "Default")
      (node (ref "Z10") (pin "5") (pinfunction "4_5") (pintype "bidirectional"))
    )
    (net (code "40") (name "DIFF_GP3_P") (class "Default")
      (node (ref "Z11") (pin "5") (pinfunction "4_5") (pintype "bidirectional"))
    )
    (net (code "41") (name "DIFF_GP4_P") (class "Default")
      (node (ref "Z12") (pin "5") (pinfunction "4_5") (pintype "bidirectional"))
    )
    (net (code "42") (name "DIFF_GP5_P") (class "Default")
      (node (ref "Z13") (pin "5") (pinfunction "4_5") (pintype "bidirectional"))
    )
    (net (code "43") (name "DOUTA_ADC_1") (class "Default")
      (node (ref "J7") (pin "21") (pinfunction "21_21") (pintype "passive"))
    )
    (net (code "44") (name "DOUTA_ADC_2") (class "Default")
      (node (ref "J7") (pin "29") (pinfunction "29_29") (pintype "passive"))
    )
    (net (code "45") (name "DOUTA_ADC_3") (class "Default")
      (node (ref "J7") (pin "37") (pinfunction "37_37") (pintype "passive"))
    )
    (net (code "46") (name "DOUTB_ADC_1") (class "Default")
      (node (ref "J7") (pin "19") (pinfunction "19_19") (pintype "passive"))
    )
    (net (code "47") (name "DOUTB_ADC_2") (class "Default")
      (node (ref "J7") (pin "27") (pinfunction "27_27") (pintype "passive"))
    )
    (net (code "48") (name "DOUTB_ADC_3") (class "Default")
      (node (ref "J7") (pin "35") (pinfunction "35_35") (pintype "passive"))
    )
    (net (code "49") (name "D_SENSE1") (class "Default")
      (node (ref "J7") (pin "26") (pinfunction "26_26") (pintype "passive"))
    )
    (net (code "50") (name "D_SENSE2") (class "Default")
      (node (ref "J7") (pin "28") (pinfunction "28_28") (pintype "passive"))
    )
    (net (code "51") (name "D_SENSE3") (class "Default")
      (node (ref "J7") (pin "30") (pinfunction "30_30") (pintype "passive"))
    )
    (net (code "52") (name "D_SENSE4") (class "Default")
      (node (ref "J7") (pin "32") (pinfunction "32_32") (pintype "passive"))
    )
    (net (code "53") (name "D_SENSE5") (class "Default")
      (node (ref "J7") (pin "34") (pinfunction "34_34") (pintype "passive"))
    )
    (net (code "54") (name "D_SENSE6") (class "Default")
      (node (ref "J7") (pin "36") (pinfunction "36_36") (pintype "passive"))
    )
    (net (code "55") (name "D_SENSE7") (class "Default")
      (node (ref "J7") (pin "38") (pinfunction "38_38") (pintype "passive"))
    )
    (net (code "56") (name "D_SENSE8") (class "Default")
      (node (ref "J7") (pin "40") (pinfunction "40_40") (pintype "passive"))
    )
    (net (code "57") (name "ETH_CRS_DV") (class "Default")
      (node (ref "UC1") (pin "PA7") (pinfunction "PA7_PA7") (pintype "passive"))
    )
    (net (code "58") (name "ETH_MDC") (class "Default")
      (node (ref "UC1") (pin "PC1") (pinfunction "PC1_PC1") (pintype "passive"))
    )
    (net (code "59") (name "ETH_MDIO") (class "Default")
      (node (ref "UC1") (pin "PA2") (pinfunction "PA2_PA2") (pintype "passive"))
    )
    (net (code "60") (name "ETH_REF_CLK") (class "Default")
      (node (ref "UC1") (pin "PA1") (pinfunction "PA1_PA1") (pintype "passive"))
    )
    (net (code "61") (name "ETH_RXD0") (class "Default")
      (node (ref "UC1") (pin "PC4") (pinfunction "PC4_PC4") (pintype "passive"))
    )
    (net (code "62") (name "ETH_RXD1") (class "Default")
      (node (ref "UC1") (pin "PC5") (pinfunction "PC5_PC5") (pintype "passive"))
    )
    (net (code "63") (name "ETH_TXD0") (class "Default")
      (node (ref "UC1") (pin "PG13") (pinfunction "PG13_PG13") (pintype "passive"))
    )
    (net (code "64") (name "ETH_TXD1") (class "Default")
      (node (ref "UC1") (pin "PB13") (pinfunction "PB13_PB13") (pintype "passive"))
    )
    (net (code "65") (name "ETH_TX_EN") (class "Default")
      (node (ref "UC1") (pin "PG11") (pinfunction "PG11_PG11") (pintype "passive"))
    )
    (net (code "66") (name "FIRSTDATA_ADC_1") (class "Default")
      (node (ref "J7") (pin "17") (pinfunction "17_17") (pintype "passive"))
    )
    (net (code "67") (name "FIRSTDATA_ADC_2") (class "Default")
      (node (ref "J7") (pin "25") (pinfunction "25_25") (pintype "passive"))
    )
    (net (code "68") (name "FIRSTDATA_ADC_3") (class "Default")
      (node (ref "J7") (pin "33") (pinfunction "33_33") (pintype "passive"))
    )
    (net (code "69") (name "FIX_NC") (class "Default")
      (node (ref "J9") (pin "06") (pinfunction "06_06") (pintype "passive"))
    )
    (net (code "70") (name "GND") (class "Default")
      (node (ref "J2") (pin "2") (pinfunction "2_2") (pintype "passive"))
      (node (ref "J2") (pin "4") (pinfunction "4_4") (pintype "passive"))
      (node (ref "J2") (pin "6") (pinfunction "6_6") (pintype "passive"))
      (node (ref "J6") (pin "02") (pinfunction "02_02") (pintype "passive"))
      (node (ref "J6") (pin "04") (pinfunction "04_04") (pintype "passive"))
      (node (ref "J6") (pin "06") (pinfunction "06_06") (pintype "passive"))
      (node (ref "J6") (pin "08") (pinfunction "08_08") (pintype "passive"))
      (node (ref "J6") (pin "22") (pinfunction "22_22") (pintype "passive"))
      (node (ref "J6") (pin "24") (pinfunction "24_24") (pintype "passive"))
      (node (ref "J6") (pin "34") (pinfunction "34_34") (pintype "passive"))
      (node (ref "J6") (pin "36") (pinfunction "36_36") (pintype "passive"))
      (node (ref "J6") (pin "38") (pinfunction "38_38") (pintype "passive"))
      (node (ref "J6") (pin "39") (pinfunction "39_39") (pintype "passive"))
      (node (ref "J6") (pin "40") (pinfunction "40_40") (pintype "passive"))
      (node (ref "J9") (pin "03") (pinfunction "03_03") (pintype "passive"))
      (node (ref "UC1") (pin "10") (pinfunction "GND_10") (pintype "passive"))
      (node (ref "UC1") (pin "122") (pinfunction "GND_122") (pintype "passive"))
      (node (ref "UC1") (pin "131") (pinfunction "GND_131") (pintype "passive"))
      (node (ref "UC1") (pin "143") (pinfunction "GND_143") (pintype "passive"))
      (node (ref "UC1") (pin "144") (pinfunction "GND_144") (pintype "passive"))
      (node (ref "UC1") (pin "19") (pinfunction "GND_19") (pintype "passive"))
      (node (ref "UC1") (pin "40") (pinfunction "GND_40") (pintype "passive"))
      (node (ref "UC1") (pin "53") (pinfunction "GND_53") (pintype "passive"))
      (node (ref "UC1") (pin "64") (pinfunction "GND_64") (pintype "passive"))
      (node (ref "UC1") (pin "71") (pinfunction "GND_71") (pintype "passive"))
      (node (ref "UC1") (pin "72") (pinfunction "GND_72") (pintype "passive"))
      (node (ref "UC1") (pin "79") (pinfunction "GND_79") (pintype "passive"))
      (node (ref "UC1") (pin "91") (pinfunction "GND_91") (pintype "passive"))
      (node (ref "UC1") (pin "92") (pinfunction "GND_92") (pintype "passive"))
      (node (ref "UC1") (pin "93") (pinfunction "GND_93") (pintype "passive"))
      (node (ref "Z10") (pin "1") (pinfunction "GND_1") (pintype "bidirectional"))
      (node (ref "Z11") (pin "1") (pinfunction "GND_1") (pintype "bidirectional"))
      (node (ref "Z12") (pin "1") (pinfunction "GND_1") (pintype "bidirectional"))
      (node (ref "Z13") (pin "1") (pinfunction "GND_1") (pintype "bidirectional"))
      (node (ref "Z14") (pin "1") (pinfunction "GND_1") (pintype "bidirectional"))
      (node (ref "Z15") (pin "1") (pinfunction "GND_1") (pintype "bidirectional"))
      (node (ref "Z16") (pin "1") (pinfunction "GND_1") (pintype "bidirectional"))
      (node (ref "Z17") (pin "1") (pinfunction "GND_1") (pintype "bidirectional"))
      (node (ref "Z18") (pin "1") (pinfunction "GND_1") (pintype "bidirectional"))
      (node (ref "Z19") (pin "1") (pinfunction "GND_1") (pintype "bidirectional"))
      (node (ref "Z20") (pin "1") (pinfunction "GND_1") (pintype "bidirectional"))
      (node (ref "Z21") (pin "1") (pinfunction "GND_1") (pintype "bidirectional"))
      (node (ref "Z22") (pin "1") (pinfunction "GND_1") (pintype "bidirectional"))
      (node (ref "Z23") (pin "1") (pinfunction "GND_1") (pintype "bidirectional"))
      (node (ref "Z24") (pin "1") (pinfunction "GND_1") (pintype "bidirectional"))
      (node (ref "Z25") (pin "1") (pinfunction "GND_1") (pintype "bidirectional"))
      (node (ref "Z26") (pin "1") (pinfunction "GND_1") (pintype "bidirectional"))
      (node (ref "Z27") (pin "1") (pinfunction "GND_1") (pintype "bidirectional"))
      (node (ref "Z28") (pin "1") (pinfunction "GND_1") (pintype "bidirectional"))
      (node (ref "Z5") (pin "1") (pinfunction "GND_1") (pintype "bidirectional"))
      (node (ref "Z6") (pin "1") (pinfunction "GND_1") (pintype "bidirectional"))
      (node (ref "Z7") (pin "1") (pinfunction "GND_1") (pintype "bidirectional"))
      (node (ref "Z8") (pin "1") (pinfunction "GND_1") (pintype "bidirectional"))
      (node (ref "Z9") (pin "1") (pinfunction "GND_1") (pintype "bidirectional"))
    )
    (net (code "71") (name "GPS_EN") (class "Default")
      (node (ref "J8") (pin "39") (pinfunction "39_39") (pintype "passive"))
      (node (ref "J9") (pin "08") (pinfunction "08_08") (pintype "passive"))
    )
    (net (code "72") (name "GPS_RX") (class "Default")
      (node (ref "J8") (pin "37") (pinfunction "37_37") (pintype "passive"))
      (node (ref "J9") (pin "04") (pinfunction "04_04") (pintype "passive"))
    )
    (net (code "73") (name "GPS_TX") (class "Default")
      (node (ref "J8") (pin "35") (pinfunction "35_35") (pintype "passive"))
      (node (ref "J9") (pin "05") (pinfunction "05_05") (pintype "passive"))
    )
    (net (code "74") (name "IMU_DIN") (class "Default")
      (node (ref "J8") (pin "05") (pinfunction "05_05") (pintype "passive"))
    )
    (net (code "75") (name "IMU_DOUT") (class "Default")
      (node (ref "J8") (pin "07") (pinfunction "07_07") (pintype "passive"))
    )
    (net (code "76") (name "IMU_DR") (class "Default")
      (node (ref "J8") (pin "13") (pinfunction "13_13") (pintype "passive"))
    )
    (net (code "77") (name "IMU_SCLK") (class "Default")
      (node (ref "J8") (pin "09") (pinfunction "09_09") (pintype "passive"))
    )
    (net (code "78") (name "IMU_SYNC") (class "Default")
      (node (ref "J8") (pin "11") (pinfunction "11_11") (pintype "passive"))
    )
    (net (code "79") (name "IP_OUT1") (class "Default")
      (node (ref "Z15") (pin "5") (pinfunction "4_5") (pintype "bidirectional"))
    )
    (net (code "80") (name "ISO_MISO") (class "Default")
      (node (ref "J8") (pin "26") (pinfunction "26_26") (pintype "passive"))
    )
    (net (code "81") (name "ISO_MOSI") (class "Default")
      (node (ref "J8") (pin "24") (pinfunction "24_24") (pintype "passive"))
    )
    (net (code "82") (name "ISO_SPI_SCLK") (class "Default")
      (node (ref "J8") (pin "22") (pinfunction "22_22") (pintype "passive"))
    )
    (net (code "83") (name "ISO_SPI_SLOW") (class "Default")
      (node (ref "J8") (pin "30") (pinfunction "30_30") (pintype "passive"))
    )
    (net (code "84") (name "LED_OUT1") (class "Default")
      (node (ref "J7") (pin "22") (pinfunction "22_22") (pintype "passive"))
    )
    (net (code "85") (name "LED_OUT2") (class "Default")
      (node (ref "J7") (pin "20") (pinfunction "20_20") (pintype "passive"))
    )
    (net (code "86") (name "LED_OUT3") (class "Default")
      (node (ref "J7") (pin "18") (pinfunction "18_18") (pintype "passive"))
    )
    (net (code "87") (name "MASS_ON") (class "Default")
      (node (ref "J8") (pin "25") (pinfunction "25_25") (pintype "passive"))
    )
    (net (code "88") (name "MUX_0") (class "Default")
      (node (ref "J8") (pin "02") (pinfunction "02_02") (pintype "passive"))
    )
    (net (code "89") (name "MUX_1") (class "Default")
      (node (ref "J8") (pin "04") (pinfunction "04_04") (pintype "passive"))
    )
    (net (code "90") (name "MUX_2") (class "Default")
      (node (ref "J8") (pin "06") (pinfunction "06_06") (pintype "passive"))
    )
    (net (code "91") (name "MUX_3") (class "Default")
      (node (ref "J8") (pin "08") (pinfunction "08_08") (pintype "passive"))
    )
    (net (code "92") (name "NAND_SPI_CLK") (class "Default")
      (node (ref "J8") (pin "12") (pinfunction "12_12") (pintype "passive"))
    )
    (net (code "93") (name "NAND_SPI_SI{slash}IO0") (class "Default")
      (node (ref "J8") (pin "14") (pinfunction "14_14") (pintype "passive"))
    )
    (net (code "94") (name "NAND_SPI_SO{slash}IO1") (class "Default")
      (node (ref "J8") (pin "16") (pinfunction "16_16") (pintype "passive"))
    )
    (net (code "95") (name "NAND_SPI_~{HOLD{slash}IO03}") (class "Default")
      (node (ref "J8") (pin "20") (pinfunction "20_20") (pintype "passive"))
    )
    (net (code "96") (name "NAND_SPI_~{WP{slash}IO2}") (class "Default")
      (node (ref "J8") (pin "18") (pinfunction "18_18") (pintype "passive"))
    )
    (net (code "97") (name "OS0_ADC") (class "Default")
      (node (ref "J7") (pin "01") (pinfunction "01_01") (pintype "passive"))
    )
    (net (code "98") (name "OS1_ADC") (class "Default")
      (node (ref "J7") (pin "03") (pinfunction "03_03") (pintype "passive"))
    )
    (net (code "99") (name "OS2_ADC") (class "Default")
      (node (ref "J7") (pin "05") (pinfunction "05_05") (pintype "passive"))
    )
    (net (code "100") (name "PA0") (class "Default")
      (node (ref "J4") (pin "01") (pinfunction "01_01") (pintype "passive"))
      (node (ref "UC1") (pin "PA0") (pinfunction "PA0_PA0") (pintype "passive"))
    )
    (net (code "101") (name "PA3") (class "Default")
      (node (ref "J4") (pin "03") (pinfunction "03_03") (pintype "passive"))
      (node (ref "UC1") (pin "PA3") (pinfunction "PA3_PA3") (pintype "passive"))
    )
    (net (code "102") (name "PA4") (class "Default")
      (node (ref "J4") (pin "05") (pinfunction "05_05") (pintype "passive"))
      (node (ref "UC1") (pin "PA4") (pinfunction "PA4_PA4") (pintype "passive"))
    )
    (net (code "103") (name "PA5") (class "Default")
      (node (ref "J4") (pin "07") (pinfunction "07_07") (pintype "passive"))
      (node (ref "UC1") (pin "PA5") (pinfunction "PA5_PA5") (pintype "passive"))
    )
    (net (code "104") (name "PA6") (class "Default")
      (node (ref "J4") (pin "09") (pinfunction "09_09") (pintype "passive"))
      (node (ref "UC1") (pin "PA6") (pinfunction "PA6_PA6") (pintype "passive"))
    )
    (net (code "105") (name "PA8") (class "Default")
      (node (ref "J4") (pin "11") (pinfunction "11_11") (pintype "passive"))
      (node (ref "UC1") (pin "PA8") (pinfunction "PA8_PA8") (pintype "passive"))
    )
    (net (code "106") (name "PA9") (class "Default")
      (node (ref "J4") (pin "13") (pinfunction "13_13") (pintype "passive"))
      (node (ref "UC1") (pin "PA9") (pinfunction "PA9_PA9") (pintype "passive"))
    )
    (net (code "107") (name "PA10") (class "Default")
      (node (ref "J4") (pin "15") (pinfunction "15_15") (pintype "passive"))
      (node (ref "UC1") (pin "PA10") (pinfunction "PA10_PA10") (pintype "passive"))
    )
    (net (code "108") (name "PA11") (class "Default")
      (node (ref "J4") (pin "17") (pinfunction "17_17") (pintype "passive"))
      (node (ref "UC1") (pin "PA11") (pinfunction "PA11_PA11") (pintype "passive"))
    )
    (net (code "109") (name "PA12") (class "Default")
      (node (ref "J4") (pin "19") (pinfunction "19_19") (pintype "passive"))
      (node (ref "UC1") (pin "PA12") (pinfunction "PA12_PA12") (pintype "passive"))
    )
    (net (code "110") (name "PA13") (class "Default")
      (node (ref "J4") (pin "21") (pinfunction "21_21") (pintype "passive"))
      (node (ref "UC1") (pin "PA13") (pinfunction "PA13_PA13") (pintype "passive"))
    )
    (net (code "111") (name "PA14") (class "Default")
      (node (ref "J4") (pin "23") (pinfunction "23_23") (pintype "passive"))
      (node (ref "UC1") (pin "PA14") (pinfunction "PA14_PA14") (pintype "passive"))
    )
    (net (code "112") (name "PA15") (class "Default")
      (node (ref "J4") (pin "25") (pinfunction "25_25") (pintype "passive"))
      (node (ref "UC1") (pin "PA15") (pinfunction "PA15_PA15") (pintype "passive"))
    )
    (net (code "113") (name "PB0") (class "Default")
      (node (ref "J4") (pin "27") (pinfunction "27_27") (pintype "passive"))
      (node (ref "UC1") (pin "PB0") (pinfunction "PB0_PB0") (pintype "passive"))
    )
    (net (code "114") (name "PB1") (class "Default")
      (node (ref "J4") (pin "29") (pinfunction "29_29") (pintype "passive"))
      (node (ref "UC1") (pin "PB1") (pinfunction "PB1_PB1") (pintype "passive"))
    )
    (net (code "115") (name "PB2") (class "Default")
      (node (ref "J4") (pin "31") (pinfunction "31_31") (pintype "passive"))
      (node (ref "UC1") (pin "PB2") (pinfunction "PB2_PB2") (pintype "passive"))
    )
    (net (code "116") (name "PB3") (class "Default")
      (node (ref "J4") (pin "33") (pinfunction "33_33") (pintype "passive"))
      (node (ref "UC1") (pin "PB3") (pinfunction "PB3_PB3") (pintype "passive"))
    )
    (net (code "117") (name "PB4") (class "Default")
      (node (ref "J4") (pin "35") (pinfunction "35_35") (pintype "passive"))
      (node (ref "UC1") (pin "PB4") (pinfunction "PB4_PB4") (pintype "passive"))
    )
    (net (code "118") (name "PB5") (class "Default")
      (node (ref "J4") (pin "37") (pinfunction "37_37") (pintype "passive"))
      (node (ref "UC1") (pin "PB5") (pinfunction "PB5_PB5") (pintype "passive"))
    )
    (net (code "119") (name "PB6") (class "Default")
      (node (ref "J4") (pin "39") (pinfunction "39_39") (pintype "passive"))
      (node (ref "UC1") (pin "PB6") (pinfunction "PB6_PB6") (pintype "passive"))
    )
    (net (code "120") (name "PB7") (class "Default")
      (node (ref "J4") (pin "40") (pinfunction "40_40") (pintype "passive"))
      (node (ref "UC1") (pin "PB7") (pinfunction "PB7_PB7") (pintype "passive"))
    )
    (net (code "121") (name "PB8") (class "Default")
      (node (ref "J4") (pin "38") (pinfunction "38_38") (pintype "passive"))
      (node (ref "UC1") (pin "PB8") (pinfunction "PB8_PB8") (pintype "passive"))
    )
    (net (code "122") (name "PB9") (class "Default")
      (node (ref "J4") (pin "36") (pinfunction "36_36") (pintype "passive"))
      (node (ref "UC1") (pin "PB9") (pinfunction "PB9_PB9") (pintype "passive"))
    )
    (net (code "123") (name "PB10") (class "Default")
      (node (ref "J4") (pin "34") (pinfunction "34_34") (pintype "passive"))
      (node (ref "UC1") (pin "PB10") (pinfunction "PB10_PB10") (pintype "passive"))
    )
    (net (code "124") (name "PB11") (class "Default")
      (node (ref "J4") (pin "32") (pinfunction "32_32") (pintype "passive"))
      (node (ref "UC1") (pin "PB11") (pinfunction "PB11_PB11") (pintype "passive"))
    )
    (net (code "125") (name "PB12") (class "Default")
      (node (ref "J4") (pin "30") (pinfunction "30_30") (pintype "passive"))
      (node (ref "UC1") (pin "PB12") (pinfunction "PB12_PB12") (pintype "passive"))
    )
    (net (code "126") (name "PB13") (class "Default")
      (node (ref "J4") (pin "28") (pinfunction "28_28") (pintype "passive"))
    )
    (net (code "127") (name "PB14") (class "Default")
      (node (ref "J4") (pin "26") (pinfunction "26_26") (pintype "passive"))
      (node (ref "UC1") (pin "PB14") (pinfunction "PB14_PB14") (pintype "passive"))
    )
    (net (code "128") (name "PB15") (class "Default")
      (node (ref "J4") (pin "24") (pinfunction "24_24") (pintype "passive"))
      (node (ref "UC1") (pin "PB15") (pinfunction "PB15_PB15") (pintype "passive"))
    )
    (net (code "129") (name "PC0") (class "Default")
      (node (ref "J4") (pin "22") (pinfunction "22_22") (pintype "passive"))
      (node (ref "UC1") (pin "PC0") (pinfunction "PC0_PC0") (pintype "passive"))
    )
    (net (code "130") (name "PC2") (class "Default")
      (node (ref "J4") (pin "20") (pinfunction "20_20") (pintype "passive"))
      (node (ref "UC1") (pin "PC2") (pinfunction "PC2_PC2") (pintype "passive"))
    )
    (net (code "131") (name "PC3") (class "Default")
      (node (ref "J4") (pin "18") (pinfunction "18_18") (pintype "passive"))
      (node (ref "UC1") (pin "PC3") (pinfunction "PC3_PC3") (pintype "passive"))
    )
    (net (code "132") (name "PC6") (class "Default")
      (node (ref "J4") (pin "16") (pinfunction "16_16") (pintype "passive"))
      (node (ref "UC1") (pin "PC6") (pinfunction "PC6_PC6") (pintype "passive"))
    )
    (net (code "133") (name "PC7") (class "Default")
      (node (ref "J4") (pin "14") (pinfunction "14_14") (pintype "passive"))
      (node (ref "UC1") (pin "PC7") (pinfunction "PC7_PC7") (pintype "passive"))
    )
    (net (code "134") (name "PC8") (class "Default")
      (node (ref "J4") (pin "12") (pinfunction "12_12") (pintype "passive"))
      (node (ref "UC1") (pin "PC8") (pinfunction "PC8_PC8") (pintype "passive"))
    )
    (net (code "135") (name "PC9") (class "Default")
      (node (ref "J4") (pin "10") (pinfunction "10_10") (pintype "passive"))
      (node (ref "UC1") (pin "PC9") (pinfunction "PC9_PC9") (pintype "passive"))
    )
    (net (code "136") (name "PC10") (class "Default")
      (node (ref "J4") (pin "08") (pinfunction "08_08") (pintype "passive"))
      (node (ref "UC1") (pin "PC10") (pinfunction "PC10_PC10") (pintype "passive"))
    )
    (net (code "137") (name "PC11") (class "Default")
      (node (ref "J4") (pin "06") (pinfunction "06_06") (pintype "passive"))
      (node (ref "UC1") (pin "PC11") (pinfunction "PC11_PC11") (pintype "passive"))
    )
    (net (code "138") (name "PC12") (class "Default")
      (node (ref "J4") (pin "04") (pinfunction "04_04") (pintype "passive"))
      (node (ref "UC1") (pin "PC12") (pinfunction "PC12_PC12") (pintype "passive"))
    )
    (net (code "139") (name "PC13") (class "Default")
      (node (ref "J4") (pin "02") (pinfunction "02_02") (pintype "passive"))
      (node (ref "UC1") (pin "PC13") (pinfunction "PC13_PC13") (pintype "passive"))
    )
    (net (code "140") (name "PC14-0SC32_IN") (class "Default")
      (node (ref "UC1") (pin "PC14") (pinfunction "PC14_PC14") (pintype "passive"))
    )
    (net (code "141") (name "PC15-OSC32_OUT") (class "Default")
      (node (ref "UC1") (pin "PC15") (pinfunction "PC15_PC15") (pintype "passive"))
    )
    (net (code "142") (name "PD0") (class "Default")
      (node (ref "J5") (pin "01") (pinfunction "01_01") (pintype "passive"))
      (node (ref "UC1") (pin "PD0") (pinfunction "PD0_PD0") (pintype "passive"))
    )
    (net (code "143") (name "PD1") (class "Default")
      (node (ref "J5") (pin "03") (pinfunction "03_03") (pintype "passive"))
      (node (ref "UC1") (pin "PD1") (pinfunction "PD1_PD1") (pintype "passive"))
    )
    (net (code "144") (name "PD2") (class "Default")
      (node (ref "J5") (pin "05") (pinfunction "05_05") (pintype "passive"))
      (node (ref "UC1") (pin "PD2") (pinfunction "PD2_PD2") (pintype "passive"))
    )
    (net (code "145") (name "PD3") (class "Default")
      (node (ref "J5") (pin "07") (pinfunction "07_07") (pintype "passive"))
      (node (ref "UC1") (pin "PD3") (pinfunction "PD3_PD3") (pintype "passive"))
    )
    (net (code "146") (name "PD4") (class "Default")
      (node (ref "J5") (pin "09") (pinfunction "09_09") (pintype "passive"))
      (node (ref "UC1") (pin "PD4") (pinfunction "PD4_PD4") (pintype "passive"))
    )
    (net (code "147") (name "PD5") (class "Default")
      (node (ref "J5") (pin "11") (pinfunction "11_11") (pintype "passive"))
      (node (ref "UC1") (pin "PD5") (pinfunction "PD5_PD5") (pintype "passive"))
    )
    (net (code "148") (name "PD6") (class "Default")
      (node (ref "J5") (pin "13") (pinfunction "13_13") (pintype "passive"))
      (node (ref "UC1") (pin "PD6") (pinfunction "PD6_PD6") (pintype "passive"))
    )
    (net (code "149") (name "PD7") (class "Default")
      (node (ref "J5") (pin "15") (pinfunction "15_15") (pintype "passive"))
      (node (ref "UC1") (pin "PD7") (pinfunction "PD7_PD7") (pintype "passive"))
    )
    (net (code "150") (name "PD11") (class "Default")
      (node (ref "J5") (pin "17") (pinfunction "17_17") (pintype "passive"))
      (node (ref "UC1") (pin "PD11") (pinfunction "PD11_PD11") (pintype "passive"))
    )
    (net (code "151") (name "PD12") (class "Default")
      (node (ref "J5") (pin "19") (pinfunction "19_19") (pintype "passive"))
      (node (ref "UC1") (pin "PD12") (pinfunction "PD12_PD12") (pintype "passive"))
    )
    (net (code "152") (name "PD13") (class "Default")
      (node (ref "J5") (pin "21") (pinfunction "21_21") (pintype "passive"))
      (node (ref "UC1") (pin "PD13") (pinfunction "PD13_PD13") (pintype "passive"))
    )
    (net (code "153") (name "PD14") (class "Default")
      (node (ref "J5") (pin "23") (pinfunction "23_23") (pintype "passive"))
      (node (ref "UC1") (pin "PD14") (pinfunction "PD14_PD14") (pintype "passive"))
    )
    (net (code "154") (name "PD15") (class "Default")
      (node (ref "J5") (pin "25") (pinfunction "25_25") (pintype "passive"))
      (node (ref "UC1") (pin "PD15") (pinfunction "PD15_PD15") (pintype "passive"))
    )
    (net (code "155") (name "PE0") (class "Default")
      (node (ref "J5") (pin "27") (pinfunction "27_27") (pintype "passive"))
      (node (ref "UC1") (pin "PE0") (pinfunction "PE0_PE0") (pintype "passive"))
    )
    (net (code "156") (name "PE1") (class "Default")
      (node (ref "J5") (pin "29") (pinfunction "29_29") (pintype "passive"))
      (node (ref "UC1") (pin "PE1") (pinfunction "PE1_PE1") (pintype "passive"))
    )
    (net (code "157") (name "PE2") (class "Default")
      (node (ref "J5") (pin "31") (pinfunction "31_31") (pintype "passive"))
      (node (ref "UC1") (pin "PE2") (pinfunction "PE2_PE2") (pintype "passive"))
    )
    (net (code "158") (name "PE3") (class "Default")
      (node (ref "J5") (pin "33") (pinfunction "33_33") (pintype "passive"))
      (node (ref "UC1") (pin "PE3") (pinfunction "PE3_PE3") (pintype "passive"))
    )
    (net (code "159") (name "PE4") (class "Default")
      (node (ref "J5") (pin "35") (pinfunction "35_35") (pintype "passive"))
      (node (ref "UC1") (pin "PE4") (pinfunction "PE4_PE4") (pintype "passive"))
    )
    (net (code "160") (name "PE5") (class "Default")
      (node (ref "J5") (pin "37") (pinfunction "37_37") (pintype "passive"))
      (node (ref "UC1") (pin "PE5") (pinfunction "PE5_PE5") (pintype "passive"))
    )
    (net (code "161") (name "PE6") (class "Default")
      (node (ref "J5") (pin "39") (pinfunction "39_39") (pintype "passive"))
      (node (ref "UC1") (pin "PE6") (pinfunction "PE6_PE6") (pintype "passive"))
    )
    (net (code "162") (name "PE7") (class "Default")
      (node (ref "J5") (pin "40") (pinfunction "40_40") (pintype "passive"))
      (node (ref "UC1") (pin "PE7") (pinfunction "PE7_PE7") (pintype "passive"))
    )
    (net (code "163") (name "PE8") (class "Default")
      (node (ref "J5") (pin "38") (pinfunction "38_38") (pintype "passive"))
      (node (ref "UC1") (pin "PE8") (pinfunction "PE8_PE8") (pintype "passive"))
    )
    (net (code "164") (name "PE9") (class "Default")
      (node (ref "J5") (pin "36") (pinfunction "36_36") (pintype "passive"))
      (node (ref "UC1") (pin "PE9") (pinfunction "PE9_PE9") (pintype "passive"))
    )
    (net (code "165") (name "PE10") (class "Default")
      (node (ref "J5") (pin "34") (pinfunction "34_34") (pintype "passive"))
      (node (ref "UC1") (pin "PE10") (pinfunction "PE10_PE10") (pintype "passive"))
    )
    (net (code "166") (name "PE11") (class "Default")
      (node (ref "J5") (pin "32") (pinfunction "32_32") (pintype "passive"))
      (node (ref "UC1") (pin "PE11") (pinfunction "PE11_PE11") (pintype "passive"))
    )
    (net (code "167") (name "PE12") (class "Default")
      (node (ref "J5") (pin "30") (pinfunction "30_30") (pintype "passive"))
      (node (ref "UC1") (pin "PE12") (pinfunction "PE12_PE12") (pintype "passive"))
    )
    (net (code "168") (name "PE13") (class "Default")
      (node (ref "J5") (pin "28") (pinfunction "28_28") (pintype "passive"))
      (node (ref "UC1") (pin "PE13") (pinfunction "PE13_PE13") (pintype "passive"))
    )
    (net (code "169") (name "PE14") (class "Default")
      (node (ref "J5") (pin "26") (pinfunction "26_26") (pintype "passive"))
      (node (ref "UC1") (pin "PE14") (pinfunction "PE14_PE14") (pintype "passive"))
    )
    (net (code "170") (name "PE15") (class "Default")
      (node (ref "J5") (pin "24") (pinfunction "24_24") (pintype "passive"))
      (node (ref "UC1") (pin "PE15") (pinfunction "PE15_PE15") (pintype "passive"))
    )
    (net (code "171") (name "PF0") (class "Default")
      (node (ref "UC1") (pin "PF0") (pinfunction "PF0_PF0") (pintype "passive"))
    )
    (net (code "172") (name "PF1") (class "Default")
      (node (ref "J5") (pin "22") (pinfunction "22_22") (pintype "passive"))
      (node (ref "UC1") (pin "PF1") (pinfunction "PF1_PF1") (pintype "passive"))
    )
    (net (code "173") (name "PF2") (class "Default")
      (node (ref "J5") (pin "20") (pinfunction "20_20") (pintype "passive"))
      (node (ref "UC1") (pin "PF2") (pinfunction "PF2_PF2") (pintype "passive"))
    )
    (net (code "174") (name "PF3") (class "Default")
      (node (ref "J5") (pin "18") (pinfunction "18_18") (pintype "passive"))
      (node (ref "UC1") (pin "PF3") (pinfunction "PF3_PF3") (pintype "passive"))
    )
    (net (code "175") (name "PF4") (class "Default")
      (node (ref "J5") (pin "16") (pinfunction "16_16") (pintype "passive"))
      (node (ref "UC1") (pin "PF4") (pinfunction "PF4_PF4") (pintype "passive"))
    )
    (net (code "176") (name "PF5") (class "Default")
      (node (ref "J5") (pin "14") (pinfunction "14_14") (pintype "passive"))
      (node (ref "UC1") (pin "PF5") (pinfunction "PF5_PF5") (pintype "passive"))
    )
    (net (code "177") (name "PF6") (class "Default")
      (node (ref "J5") (pin "12") (pinfunction "12_12") (pintype "passive"))
      (node (ref "UC1") (pin "PF6") (pinfunction "PF6_PF6") (pintype "passive"))
    )
    (net (code "178") (name "PF7") (class "Default")
      (node (ref "J5") (pin "10") (pinfunction "10_10") (pintype "passive"))
      (node (ref "UC1") (pin "PF7") (pinfunction "PF7_PF7") (pintype "passive"))
    )
    (net (code "179") (name "PF8") (class "Default")
      (node (ref "J5") (pin "08") (pinfunction "08_08") (pintype "passive"))
      (node (ref "UC1") (pin "PF8") (pinfunction "PF8_PF8") (pintype "passive"))
    )
    (net (code "180") (name "PF9") (class "Default")
      (node (ref "J5") (pin "06") (pinfunction "06_06") (pintype "passive"))
      (node (ref "UC1") (pin "PF9") (pinfunction "PF9_PF9") (pintype "passive"))
    )
    (net (code "181") (name "PF10") (class "Default")
      (node (ref "J5") (pin "04") (pinfunction "04_04") (pintype "passive"))
      (node (ref "UC1") (pin "PF10") (pinfunction "PF10_PF10") (pintype "passive"))
    )
    (net (code "182") (name "PF11") (class "Default")
      (node (ref "J5") (pin "02") (pinfunction "02_02") (pintype "passive"))
      (node (ref "UC1") (pin "PF11") (pinfunction "PF11_PF11") (pintype "passive"))
    )
    (net (code "183") (name "PF12") (class "Default")
      (node (ref "J6") (pin "01") (pinfunction "01_01") (pintype "passive"))
      (node (ref "UC1") (pin "PF12") (pinfunction "PF12_PF12") (pintype "passive"))
    )
    (net (code "184") (name "PF13") (class "Default")
      (node (ref "J6") (pin "03") (pinfunction "03_03") (pintype "passive"))
      (node (ref "UC1") (pin "PF13") (pinfunction "PF13_PF13") (pintype "passive"))
    )
    (net (code "185") (name "PF14") (class "Default")
      (node (ref "J6") (pin "05") (pinfunction "05_05") (pintype "passive"))
      (node (ref "UC1") (pin "PF14") (pinfunction "PF14_PF14") (pintype "passive"))
    )
    (net (code "186") (name "PF15") (class "Default")
      (node (ref "J6") (pin "07") (pinfunction "07_07") (pintype "passive"))
      (node (ref "UC1") (pin "PF15") (pinfunction "PF15_PF15") (pintype "passive"))
    )
    (net (code "187") (name "PG0") (class "Default")
      (node (ref "J6") (pin "09") (pinfunction "09_09") (pintype "passive"))
      (node (ref "UC1") (pin "PG0") (pinfunction "PG0_PG0") (pintype "passive"))
    )
    (net (code "188") (name "PG1") (class "Default")
      (node (ref "J6") (pin "11") (pinfunction "11_11") (pintype "passive"))
      (node (ref "UC1") (pin "PG1") (pinfunction "PG1_PG1") (pintype "passive"))
    )
    (net (code "189") (name "PG2") (class "Default")
      (node (ref "J6") (pin "13") (pinfunction "13_13") (pintype "passive"))
      (node (ref "UC1") (pin "PG2") (pinfunction "PG2_PG2") (pintype "passive"))
    )
    (net (code "190") (name "PG3") (class "Default")
      (node (ref "J6") (pin "15") (pinfunction "15_15") (pintype "passive"))
      (node (ref "UC1") (pin "PG3") (pinfunction "PG3_PG3") (pintype "passive"))
    )
    (net (code "191") (name "PG4") (class "Default")
      (node (ref "J6") (pin "17") (pinfunction "17_17") (pintype "passive"))
      (node (ref "UC1") (pin "PG4") (pinfunction "PG4_PG4") (pintype "passive"))
    )
    (net (code "192") (name "PG5") (class "Default")
      (node (ref "J6") (pin "19") (pinfunction "19_19") (pintype "passive"))
      (node (ref "UC1") (pin "PG5") (pinfunction "PG5_PG5") (pintype "passive"))
    )
    (net (code "193") (name "PG6") (class "Default")
      (node (ref "J6") (pin "21") (pinfunction "21_21") (pintype "passive"))
      (node (ref "UC1") (pin "PG6") (pinfunction "PG6_PG6") (pintype "passive"))
    )
    (net (code "194") (name "PG7") (class "Default")
      (node (ref "J6") (pin "23") (pinfunction "23_23") (pintype "passive"))
    )
    (net (code "195") (name "PG8") (class "Default")
      (node (ref "J6") (pin "25") (pinfunction "25_25") (pintype "passive"))
      (node (ref "UC1") (pin "PG8") (pinfunction "PG8_PG8") (pintype "passive"))
    )
    (net (code "196") (name "PG9") (class "Default")
      (node (ref "J6") (pin "27") (pinfunction "27_27") (pintype "passive"))
      (node (ref "UC1") (pin "PG9") (pinfunction "PG9_PG9") (pintype "passive"))
    )
    (net (code "197") (name "PG10") (class "Default")
      (node (ref "J6") (pin "29") (pinfunction "29_29") (pintype "passive"))
      (node (ref "UC1") (pin "PG10") (pinfunction "PG10_PG10") (pintype "passive"))
    )
    (net (code "198") (name "PG12") (class "Default")
      (node (ref "J6") (pin "31") (pinfunction "31_31") (pintype "passive"))
      (node (ref "UC1") (pin "PG12") (pinfunction "PG12_PG12") (pintype "passive"))
    )
    (net (code "199") (name "PG14") (class "Default")
      (node (ref "J6") (pin "33") (pinfunction "33_33") (pintype "passive"))
      (node (ref "UC1") (pin "PG14") (pinfunction "PG14_PG14") (pintype "passive"))
    )
    (net (code "200") (name "PG15") (class "Default")
      (node (ref "J6") (pin "35") (pinfunction "35_35") (pintype "passive"))
      (node (ref "UC1") (pin "PG15") (pinfunction "PG15_PG15") (pintype "passive"))
    )
    (net (code "201") (name "PH0-OSC_IN") (class "Default")
      (node (ref "UC1") (pin "PH0") (pinfunction "PH0_PH0") (pintype "passive"))
    )
    (net (code "202") (name "PH1") (class "Default")
      (node (ref "J6") (pin "37") (pinfunction "37_37") (pintype "passive"))
      (node (ref "UC1") (pin "PH1") (pinfunction "PH1_PH1") (pintype "passive"))
    )
    (net (code "203") (name "POWER_FAULT1") (class "Default")
      (node (ref "J2") (pin "7") (pinfunction "7_7") (pintype "passive"))
      (node (ref "J8") (pin "15") (pinfunction "15_15") (pintype "passive"))
    )
    (net (code "204") (name "POWER_FAULT2") (class "Default")
      (node (ref "J2") (pin "9") (pinfunction "9_9") (pintype "passive"))
      (node (ref "J8") (pin "17") (pinfunction "17_17") (pintype "passive"))
    )
    (net (code "205") (name "POWER_FAULT3") (class "Default")
      (node (ref "J2") (pin "11") (pinfunction "11_11") (pintype "passive"))
      (node (ref "J8") (pin "19") (pinfunction "19_19") (pintype "passive"))
    )
    (net (code "206") (name "PPS_NC") (class "Default")
      (node (ref "J9") (pin "01") (pinfunction "01_01") (pintype "passive"))
    )
    (net (code "207") (name "P_LED") (class "Default")
      (node (ref "J7") (pin "24") (pinfunction "24_24") (pintype "passive"))
    )
    (net (code "208") (name "RESET_ADC") (class "Default")
      (node (ref "J7") (pin "09") (pinfunction "09_09") (pintype "passive"))
    )
    (net (code "209") (name "SCL1") (class "Default")
      (node (ref "J8") (pin "23") (pinfunction "23_23") (pintype "passive"))
    )
    (net (code "210") (name "SCL2") (class "Default")
      (node (ref "J8") (pin "29") (pinfunction "29_29") (pintype "passive"))
    )
    (net (code "211") (name "SCLK_ADC") (class "Default")
      (node (ref "J7") (pin "11") (pinfunction "11_11") (pintype "passive"))
    )
    (net (code "212") (name "SDA1") (class "Default")
      (node (ref "J8") (pin "21") (pinfunction "21_21") (pintype "passive"))
    )
    (net (code "213") (name "SDA2") (class "Default")
      (node (ref "J8") (pin "27") (pinfunction "27_27") (pintype "passive"))
    )
    (net (code "214") (name "SOURCE1_") (class "Default")
      (node (ref "Z1") (pin "2") (pinfunction "1_2") (pintype "bidirectional"))
    )
    (net (code "215") (name "SOURCE1_0") (class "Default")
      (node (ref "Z3") (pin "2") (pinfunction "1_2") (pintype "bidirectional"))
    )
    (net (code "216") (name "SOURCE1_1") (class "Default")
      (node (ref "Z21") (pin "2") (pinfunction "1_2") (pintype "bidirectional"))
    )
    (net (code "217") (name "SOURCE1_2") (class "Default")
      (node (ref "Z23") (pin "2") (pinfunction "1_2") (pintype "bidirectional"))
    )
    (net (code "218") (name "SOURCE1_3") (class "Default")
      (node (ref "Z5") (pin "2") (pinfunction "1_2") (pintype "bidirectional"))
    )
    (net (code "219") (name "SOURCE1_4") (class "Default")
      (node (ref "Z7") (pin "2") (pinfunction "1_2") (pintype "bidirectional"))
    )
    (net (code "220") (name "SOURCE1_5") (class "Default")
      (node (ref "Z17") (pin "2") (pinfunction "1_2") (pintype "bidirectional"))
    )
    (net (code "221") (name "SOURCE1_6") (class "Default")
      (node (ref "Z19") (pin "2") (pinfunction "1_2") (pintype "bidirectional"))
    )
    (net (code "222") (name "SOURCE1_7") (class "Default")
      (node (ref "Z9") (pin "2") (pinfunction "1_2") (pintype "bidirectional"))
    )
    (net (code "223") (name "SOURCE1_8") (class "Default")
      (node (ref "Z11") (pin "2") (pinfunction "1_2") (pintype "bidirectional"))
    )
    (net (code "224") (name "SOURCE1_9") (class "Default")
      (node (ref "Z13") (pin "2") (pinfunction "1_2") (pintype "bidirectional"))
    )
    (net (code "225") (name "SOURCE1_10") (class "Default")
      (node (ref "Z15") (pin "2") (pinfunction "1_2") (pintype "bidirectional"))
    )
    (net (code "226") (name "SOURCE1_11") (class "Default")
      (node (ref "Z25") (pin "2") (pinfunction "1_2") (pintype "bidirectional"))
      (node (ref "Z25") (pin "5") (pinfunction "4_5") (pintype "bidirectional"))
    )
    (net (code "227") (name "SOURCE1_12") (class "Default")
      (node (ref "Z27") (pin "2") (pinfunction "1_2") (pintype "bidirectional"))
      (node (ref "Z27") (pin "5") (pinfunction "4_5") (pintype "bidirectional"))
    )
    (net (code "228") (name "SOURCE2_") (class "Default")
      (node (ref "Z2") (pin "2") (pinfunction "1_2") (pintype "bidirectional"))
    )
    (net (code "229") (name "SOURCE2_0") (class "Default")
      (node (ref "Z4") (pin "2") (pinfunction "1_2") (pintype "bidirectional"))
    )
    (net (code "230") (name "SOURCE2_1") (class "Default")
      (node (ref "Z22") (pin "2") (pinfunction "1_2") (pintype "bidirectional"))
    )
    (net (code "231") (name "SOURCE2_2") (class "Default")
      (node (ref "Z24") (pin "2") (pinfunction "1_2") (pintype "bidirectional"))
    )
    (net (code "232") (name "SOURCE2_3") (class "Default")
      (node (ref "Z6") (pin "2") (pinfunction "1_2") (pintype "bidirectional"))
    )
    (net (code "233") (name "SOURCE2_4") (class "Default")
      (node (ref "Z8") (pin "2") (pinfunction "1_2") (pintype "bidirectional"))
    )
    (net (code "234") (name "SOURCE2_5") (class "Default")
      (node (ref "Z18") (pin "2") (pinfunction "1_2") (pintype "bidirectional"))
    )
    (net (code "235") (name "SOURCE2_6") (class "Default")
      (node (ref "Z20") (pin "2") (pinfunction "1_2") (pintype "bidirectional"))
    )
    (net (code "236") (name "SOURCE2_7") (class "Default")
      (node (ref "Z10") (pin "2") (pinfunction "1_2") (pintype "bidirectional"))
    )
    (net (code "237") (name "SOURCE2_8") (class "Default")
      (node (ref "Z12") (pin "2") (pinfunction "1_2") (pintype "bidirectional"))
    )
    (net (code "238") (name "SOURCE2_9") (class "Default")
      (node (ref "Z14") (pin "2") (pinfunction "1_2") (pintype "bidirectional"))
    )
    (net (code "239") (name "SOURCE2_10") (class "Default")
      (node (ref "Z16") (pin "2") (pinfunction "1_2") (pintype "bidirectional"))
    )
    (net (code "240") (name "SOURCE2_11") (class "Default")
      (node (ref "Z26") (pin "2") (pinfunction "1_2") (pintype "bidirectional"))
      (node (ref "Z26") (pin "5") (pinfunction "4_5") (pintype "bidirectional"))
    )
    (net (code "241") (name "SOURCE2_12") (class "Default")
      (node (ref "Z28") (pin "2") (pinfunction "1_2") (pintype "bidirectional"))
      (node (ref "Z28") (pin "5") (pinfunction "4_5") (pintype "bidirectional"))
    )
    (net (code "242") (name "THERMOCOUPLE_MISO") (class "Default")
      (node (ref "J8") (pin "34") (pinfunction "34_34") (pintype "passive"))
    )
    (net (code "243") (name "THERMOCOUPLE_SCLK") (class "Default")
      (node (ref "J8") (pin "32") (pinfunction "32_32") (pintype "passive"))
    )
    (net (code "244") (name "USART3_TX") (class "Default")
      (node (ref "UC1") (pin "PD8") (pinfunction "PD8_PD8") (pintype "passive"))
    )
    (net (code "245") (name "USART4_RX") (class "Default")
      (node (ref "UC1") (pin "PD9") (pinfunction "PD9_PD9") (pintype "passive"))
    )
    (net (code "246") (name "USB_FS_OVCR") (class "Default")
      (node (ref "UC1") (pin "PG7") (pinfunction "PG7_PG7") (pintype "passive"))
    )
    (net (code "247") (name "USB_FS_PWR_EN") (class "Default")
      (node (ref "UC1") (pin "PD10") (pinfunction "PD10_PD10") (pintype "passive"))
    )
    (net (code "248") (name "VBAT_NC") (class "Default")
      (node (ref "J9") (pin "07") (pinfunction "07_07") (pintype "passive"))
    )
    (net (code "249") (name "unconnected-(J1-Pad2)") (class "Default")
      (node (ref "J1") (pin "2") (pinfunction "2_2") (pintype "passive"))
    )
    (net (code "250") (name "unconnected-(J1-Pad4)") (class "Default")
      (node (ref "J1") (pin "4") (pinfunction "4_4") (pintype "passive"))
    )
    (net (code "251") (name "unconnected-(J1-Pad6)") (class "Default")
      (node (ref "J1") (pin "6") (pinfunction "6_6") (pintype "passive"))
    )
    (net (code "252") (name "unconnected-(J1-Pad8)") (class "Default")
      (node (ref "J1") (pin "8") (pinfunction "8_8") (pintype "passive"))
    )
    (net (code "253") (name "unconnected-(J7-Pad02)") (class "Default")
      (node (ref "J7") (pin "02") (pinfunction "02_02") (pintype "passive"))
    )
    (net (code "254") (name "unconnected-(J7-Pad04)") (class "Default")
      (node (ref "J7") (pin "04") (pinfunction "04_04") (pintype "passive"))
    )
    (net (code "255") (name "unconnected-(J7-Pad06)") (class "Default")
      (node (ref "J7") (pin "06") (pinfunction "06_06") (pintype "passive"))
    )
    (net (code "256") (name "unconnected-(J7-Pad08)") (class "Default")
      (node (ref "J7") (pin "08") (pinfunction "08_08") (pintype "passive"))
    )
    (net (code "257") (name "unconnected-(J7-Pad10)") (class "Default")
      (node (ref "J7") (pin "10") (pinfunction "10_10") (pintype "passive"))
    )
    (net (code "258") (name "unconnected-(J7-Pad12)") (class "Default")
      (node (ref "J7") (pin "12") (pinfunction "12_12") (pintype "passive"))
    )
    (net (code "259") (name "unconnected-(J7-Pad14)") (class "Default")
      (node (ref "J7") (pin "14") (pinfunction "14_14") (pintype "passive"))
    )
    (net (code "260") (name "unconnected-(J7-Pad16)") (class "Default")
      (node (ref "J7") (pin "16") (pinfunction "16_16") (pintype "passive"))
    )
    (net (code "261") (name "unconnected-(J7-Pad39)") (class "Default")
      (node (ref "J7") (pin "39") (pinfunction "39_39") (pintype "passive"))
    )
    (net (code "262") (name "unconnected-(J8-Pad31)") (class "Default")
      (node (ref "J8") (pin "31") (pinfunction "31_31") (pintype "passive"))
    )
    (net (code "263") (name "unconnected-(J8-Pad33)") (class "Default")
      (node (ref "J8") (pin "33") (pinfunction "33_33") (pintype "passive"))
    )
    (net (code "264") (name "unconnected-(J8-Pad38)") (class "Default")
      (node (ref "J8") (pin "38") (pinfunction "38_38") (pintype "passive"))
    )
    (net (code "265") (name "unconnected-(J8-Pad40)") (class "Default")
      (node (ref "J8") (pin "40") (pinfunction "40_40") (pintype "passive"))
    )
    (net (code "266") (name "unconnected-(U$5-THROUGH_HOLE-Pad1{slash}16IN)") (class "Default")
      (node (ref "U$5") (pin "1/16IN") (pinfunction "THROUGH_HOLE_1/16IN") (pintype "bidirectional"))
    )
    (net (code "267") (name "unconnected-(U$6-THROUGH_HOLE-Pad1{slash}16IN)") (class "Default")
      (node (ref "U$6") (pin "1/16IN") (pinfunction "THROUGH_HOLE_1/16IN") (pintype "bidirectional"))
    )
    (net (code "268") (name "unconnected-(U$7-THROUGH_HOLE-Pad1{slash}16IN)") (class "Default")
      (node (ref "U$7") (pin "1/16IN") (pinfunction "THROUGH_HOLE_1/16IN") (pintype "bidirectional"))
    )
    (net (code "269") (name "unconnected-(U$8-THROUGH_HOLE-Pad1{slash}16IN)") (class "Default")
      (node (ref "U$8") (pin "1/16IN") (pinfunction "THROUGH_HOLE_1/16IN") (pintype "bidirectional"))
    )
    (net (code "270") (name "unconnected-(U$9-THROUGH_HOLE-Pad1{slash}16IN)") (class "Default")
      (node (ref "U$9") (pin "1/16IN") (pinfunction "THROUGH_HOLE_1/16IN") (pintype "bidirectional"))
    )
    (net (code "271") (name "unconnected-(U$10-THROUGH_HOLE-Pad1{slash}16IN)") (class "Default")
      (node (ref "U$10") (pin "1/16IN") (pinfunction "THROUGH_HOLE_1/16IN") (pintype "bidirectional"))
    )
    (net (code "272") (name "unconnected-(U$12-THROUGH_HOLE-Pad1{slash}16IN)") (class "Default")
      (node (ref "U$12") (pin "1/16IN") (pinfunction "THROUGH_HOLE_1/16IN") (pintype "bidirectional"))
    )
    (net (code "273") (name "unconnected-(U$13-THROUGH_HOLE-Pad1{slash}16IN)") (class "Default")
      (node (ref "U$13") (pin "1/16IN") (pinfunction "THROUGH_HOLE_1/16IN") (pintype "bidirectional"))
    )
    (net (code "274") (name "unconnected-(U$14-THROUGH_HOLE-Pad1{slash}16IN)") (class "Default")
      (node (ref "U$14") (pin "1/16IN") (pinfunction "THROUGH_HOLE_1/16IN") (pintype "bidirectional"))
    )
    (net (code "275") (name "unconnected-(U$15-THROUGH_HOLE-Pad1{slash}16IN)") (class "Default")
      (node (ref "U$15") (pin "1/16IN") (pinfunction "THROUGH_HOLE_1/16IN") (pintype "bidirectional"))
    )
    (net (code "276") (name "unconnected-(UC1-AGND-Pad31_AGND)") (class "Default")
      (node (ref "UC1") (pin "31_AGND") (pinfunction "AGND_31_AGND") (pintype "passive"))
    )
    (net (code "277") (name "unconnected-(UC1-Pad3V3)") (class "Default")
      (node (ref "UC1") (pin "3V3") (pinfunction "3V3_3V3") (pintype "passive"))
    )
    (net (code "278") (name "unconnected-(UC1-Pad5V)") (class "Default")
      (node (ref "UC1") (pin "5V") (pinfunction "5V_5V") (pintype "passive"))
    )
    (net (code "279") (name "unconnected-(UC1-Pad5V_USB_STLK)") (class "Default")
      (node (ref "UC1") (pin "5V_USB_STLK") (pinfunction "5V_USB_STLK_5V_USB_STLK") (pintype "passive"))
    )
    (net (code "280") (name "unconnected-(UC1-PadBOOT0)") (class "Default")
      (node (ref "UC1") (pin "BOOT0") (pinfunction "BOOT0_BOOT0") (pintype "passive"))
    )
    (net (code "281") (name "unconnected-(UC1-PadIOREF)") (class "Default")
      (node (ref "UC1") (pin "IOREF") (pinfunction "IOREF_IOREF") (pintype "passive"))
    )
    (net (code "282") (name "unconnected-(UC1-PadNC_1)") (class "Default")
      (node (ref "UC1") (pin "NC_1") (pinfunction "NC_1_NC_1") (pintype "passive"))
    )
    (net (code "283") (name "unconnected-(UC1-PadNC_2)") (class "Default")
      (node (ref "UC1") (pin "NC_2") (pinfunction "NC_2_NC_2") (pintype "passive"))
    )
    (net (code "284") (name "unconnected-(UC1-PadNC_3)") (class "Default")
      (node (ref "UC1") (pin "NC_3") (pinfunction "NC_3_NC_3") (pintype "passive"))
    )
    (net (code "285") (name "unconnected-(UC1-PadNRST)") (class "Default")
      (node (ref "UC1") (pin "NRST") (pinfunction "NRST_NRST") (pintype "passive"))
    )
    (net (code "286") (name "unconnected-(UC1-PadVBAT)") (class "Default")
      (node (ref "UC1") (pin "VBAT") (pinfunction "VBAT_VBAT") (pintype "passive"))
    )
    (net (code "287") (name "unconnected-(UC1-PadVIN)") (class "Default")
      (node (ref "UC1") (pin "VIN") (pinfunction "VIN_VIN") (pintype "passive"))
    )
    (net (code "288") (name "unconnected-(UC1-PadVREFP)") (class "Default")
      (node (ref "UC1") (pin "VREFP") (pinfunction "VREFP_VREFP") (pintype "passive"))
    )
    (net (code "289") (name "unconnected-(Z1-2-Pad3)") (class "Default")
      (node (ref "Z1") (pin "3") (pinfunction "2_3") (pintype "bidirectional"))
    )
    (net (code "290") (name "unconnected-(Z1-3-Pad4)") (class "Default")
      (node (ref "Z1") (pin "4") (pinfunction "3_4") (pintype "bidirectional"))
    )
    (net (code "291") (name "unconnected-(Z1-GND-Pad1)") (class "Default")
      (node (ref "Z1") (pin "1") (pinfunction "GND_1") (pintype "bidirectional"))
    )
    (net (code "292") (name "unconnected-(Z2-2-Pad3)") (class "Default")
      (node (ref "Z2") (pin "3") (pinfunction "2_3") (pintype "bidirectional"))
    )
    (net (code "293") (name "unconnected-(Z2-3-Pad4)") (class "Default")
      (node (ref "Z2") (pin "4") (pinfunction "3_4") (pintype "bidirectional"))
    )
    (net (code "294") (name "unconnected-(Z2-GND-Pad1)") (class "Default")
      (node (ref "Z2") (pin "1") (pinfunction "GND_1") (pintype "bidirectional"))
    )
    (net (code "295") (name "unconnected-(Z3-2-Pad3)") (class "Default")
      (node (ref "Z3") (pin "3") (pinfunction "2_3") (pintype "bidirectional"))
    )
    (net (code "296") (name "unconnected-(Z3-3-Pad4)") (class "Default")
      (node (ref "Z3") (pin "4") (pinfunction "3_4") (pintype "bidirectional"))
    )
    (net (code "297") (name "unconnected-(Z3-GND-Pad1)") (class "Default")
      (node (ref "Z3") (pin "1") (pinfunction "GND_1") (pintype "bidirectional"))
    )
    (net (code "298") (name "unconnected-(Z4-2-Pad3)") (class "Default")
      (node (ref "Z4") (pin "3") (pinfunction "2_3") (pintype "bidirectional"))
    )
    (net (code "299") (name "unconnected-(Z4-3-Pad4)") (class "Default")
      (node (ref "Z4") (pin "4") (pinfunction "3_4") (pintype "bidirectional"))
    )
    (net (code "300") (name "unconnected-(Z4-GND-Pad1)") (class "Default")
      (node (ref "Z4") (pin "1") (pinfunction "GND_1") (pintype "bidirectional"))
    )
    (net (code "301") (name "unconnected-(Z5-2-Pad3)") (class "Default")
      (node (ref "Z5") (pin "3") (pinfunction "2_3") (pintype "bidirectional"))
    )
    (net (code "302") (name "unconnected-(Z5-3-Pad4)") (class "Default")
      (node (ref "Z5") (pin "4") (pinfunction "3_4") (pintype "bidirectional"))
    )
    (net (code "303") (name "unconnected-(Z6-2-Pad3)") (class "Default")
      (node (ref "Z6") (pin "3") (pinfunction "2_3") (pintype "bidirectional"))
    )
    (net (code "304") (name "unconnected-(Z6-3-Pad4)") (class "Default")
      (node (ref "Z6") (pin "4") (pinfunction "3_4") (pintype "bidirectional"))
    )
    (net (code "305") (name "unconnected-(Z7-2-Pad3)") (class "Default")
      (node (ref "Z7") (pin "3") (pinfunction "2_3") (pintype "bidirectional"))
    )
    (net (code "306") (name "unconnected-(Z7-3-Pad4)") (class "Default")
      (node (ref "Z7") (pin "4") (pinfunction "3_4") (pintype "bidirectional"))
    )
    (net (code "307") (name "unconnected-(Z8-2-Pad3)") (class "Default")
      (node (ref "Z8") (pin "3") (pinfunction "2_3") (pintype "bidirectional"))
    )
    (net (code "308") (name "unconnected-(Z8-3-Pad4)") (class "Default")
      (node (ref "Z8") (pin "4") (pinfunction "3_4") (pintype "bidirectional"))
    )
    (net (code "309") (name "unconnected-(Z9-2-Pad3)") (class "Default")
      (node (ref "Z9") (pin "3") (pinfunction "2_3") (pintype "bidirectional"))
    )
    (net (code "310") (name "unconnected-(Z9-3-Pad4)") (class "Default")
      (node (ref "Z9") (pin "4") (pinfunction "3_4") (pintype "bidirectional"))
    )
    (net (code "311") (name "unconnected-(Z10-2-Pad3)") (class "Default")
      (node (ref "Z10") (pin "3") (pinfunction "2_3") (pintype "bidirectional"))
    )
    (net (code "312") (name "unconnected-(Z10-3-Pad4)") (class "Default")
      (node (ref "Z10") (pin "4") (pinfunction "3_4") (pintype "bidirectional"))
    )
    (net (code "313") (name "unconnected-(Z11-2-Pad3)") (class "Default")
      (node (ref "Z11") (pin "3") (pinfunction "2_3") (pintype "bidirectional"))
    )
    (net (code "314") (name "unconnected-(Z11-3-Pad4)") (class "Default")
      (node (ref "Z11") (pin "4") (pinfunction "3_4") (pintype "bidirectional"))
    )
    (net (code "315") (name "unconnected-(Z12-2-Pad3)") (class "Default")
      (node (ref "Z12") (pin "3") (pinfunction "2_3") (pintype "bidirectional"))
    )
    (net (code "316") (name "unconnected-(Z12-3-Pad4)") (class "Default")
      (node (ref "Z12") (pin "4") (pinfunction "3_4") (pintype "bidirectional"))
    )
    (net (code "317") (name "unconnected-(Z13-2-Pad3)") (class "Default")
      (node (ref "Z13") (pin "3") (pinfunction "2_3") (pintype "bidirectional"))
    )
    (net (code "318") (name "unconnected-(Z13-3-Pad4)") (class "Default")
      (node (ref "Z13") (pin "4") (pinfunction "3_4") (pintype "bidirectional"))
    )
    (net (code "319") (name "unconnected-(Z14-2-Pad3)") (class "Default")
      (node (ref "Z14") (pin "3") (pinfunction "2_3") (pintype "bidirectional"))
    )
    (net (code "320") (name "unconnected-(Z14-3-Pad4)") (class "Default")
      (node (ref "Z14") (pin "4") (pinfunction "3_4") (pintype "bidirectional"))
    )
    (net (code "321") (name "unconnected-(Z15-2-Pad3)") (class "Default")
      (node (ref "Z15") (pin "3") (pinfunction "2_3") (pintype "bidirectional"))
    )
    (net (code "322") (name "unconnected-(Z15-3-Pad4)") (class "Default")
      (node (ref "Z15") (pin "4") (pinfunction "3_4") (pintype "bidirectional"))
    )
    (net (code "323") (name "unconnected-(Z16-2-Pad3)") (class "Default")
      (node (ref "Z16") (pin "3") (pinfunction "2_3") (pintype "bidirectional"))
    )
    (net (code "324") (name "unconnected-(Z16-3-Pad4)") (class "Default")
      (node (ref "Z16") (pin "4") (pinfunction "3_4") (pintype "bidirectional"))
    )
    (net (code "325") (name "unconnected-(Z17-2-Pad3)") (class "Default")
      (node (ref "Z17") (pin "3") (pinfunction "2_3") (pintype "bidirectional"))
    )
    (net (code "326") (name "unconnected-(Z17-3-Pad4)") (class "Default")
      (node (ref "Z17") (pin "4") (pinfunction "3_4") (pintype "bidirectional"))
    )
    (net (code "327") (name "unconnected-(Z18-2-Pad3)") (class "Default")
      (node (ref "Z18") (pin "3") (pinfunction "2_3") (pintype "bidirectional"))
    )
    (net (code "328") (name "unconnected-(Z18-3-Pad4)") (class "Default")
      (node (ref "Z18") (pin "4") (pinfunction "3_4") (pintype "bidirectional"))
    )
    (net (code "329") (name "unconnected-(Z19-2-Pad3)") (class "Default")
      (node (ref "Z19") (pin "3") (pinfunction "2_3") (pintype "bidirectional"))
    )
    (net (code "330") (name "unconnected-(Z19-3-Pad4)") (class "Default")
      (node (ref "Z19") (pin "4") (pinfunction "3_4") (pintype "bidirectional"))
    )
    (net (code "331") (name "unconnected-(Z20-2-Pad3)") (class "Default")
      (node (ref "Z20") (pin "3") (pinfunction "2_3") (pintype "bidirectional"))
    )
    (net (code "332") (name "unconnected-(Z20-3-Pad4)") (class "Default")
      (node (ref "Z20") (pin "4") (pinfunction "3_4") (pintype "bidirectional"))
    )
    (net (code "333") (name "unconnected-(Z21-2-Pad3)") (class "Default")
      (node (ref "Z21") (pin "3") (pinfunction "2_3") (pintype "bidirectional"))
    )
    (net (code "334") (name "unconnected-(Z21-3-Pad4)") (class "Default")
      (node (ref "Z21") (pin "4") (pinfunction "3_4") (pintype "bidirectional"))
    )
    (net (code "335") (name "unconnected-(Z22-2-Pad3)") (class "Default")
      (node (ref "Z22") (pin "3") (pinfunction "2_3") (pintype "bidirectional"))
    )
    (net (code "336") (name "unconnected-(Z22-3-Pad4)") (class "Default")
      (node (ref "Z22") (pin "4") (pinfunction "3_4") (pintype "bidirectional"))
    )
    (net (code "337") (name "unconnected-(Z23-2-Pad3)") (class "Default")
      (node (ref "Z23") (pin "3") (pinfunction "2_3") (pintype "bidirectional"))
    )
    (net (code "338") (name "unconnected-(Z23-3-Pad4)") (class "Default")
      (node (ref "Z23") (pin "4") (pinfunction "3_4") (pintype "bidirectional"))
    )
    (net (code "339") (name "unconnected-(Z24-2-Pad3)") (class "Default")
      (node (ref "Z24") (pin "3") (pinfunction "2_3") (pintype "bidirectional"))
    )
    (net (code "340") (name "unconnected-(Z24-3-Pad4)") (class "Default")
      (node (ref "Z24") (pin "4") (pinfunction "3_4") (pintype "bidirectional"))
    )
    (net (code "341") (name "unconnected-(Z25-2-Pad3)") (class "Default")
      (node (ref "Z25") (pin "3") (pinfunction "2_3") (pintype "bidirectional"))
    )
    (net (code "342") (name "unconnected-(Z25-3-Pad4)") (class "Default")
      (node (ref "Z25") (pin "4") (pinfunction "3_4") (pintype "bidirectional"))
    )
    (net (code "343") (name "unconnected-(Z26-2-Pad3)") (class "Default")
      (node (ref "Z26") (pin "3") (pinfunction "2_3") (pintype "bidirectional"))
    )
    (net (code "344") (name "unconnected-(Z26-3-Pad4)") (class "Default")
      (node (ref "Z26") (pin "4") (pinfunction "3_4") (pintype "bidirectional"))
    )
    (net (code "345") (name "unconnected-(Z27-2-Pad3)") (class "Default")
      (node (ref "Z27") (pin "3") (pinfunction "2_3") (pintype "bidirectional"))
    )
    (net (code "346") (name "unconnected-(Z27-3-Pad4)") (class "Default")
      (node (ref "Z27") (pin "4") (pinfunction "3_4") (pintype "bidirectional"))
    )
    (net (code "347") (name "unconnected-(Z28-2-Pad3)") (class "Default")
      (node (ref "Z28") (pin "3") (pinfunction "2_3") (pintype "bidirectional"))
    )
    (net (code "348") (name "unconnected-(Z28-3-Pad4)") (class "Default")
      (node (ref "Z28") (pin "4") (pinfunction "3_4") (pintype "bidirectional"))
    )
    (net (code "349") (name "~{CS_ADC}") (class "Default")
      (node (ref "J7") (pin "13") (pinfunction "13_13") (pintype "passive"))
    )
    (net (code "350") (name "~{CS_INPUT_NAND}") (class "Default")
      (node (ref "J8") (pin "10") (pinfunction "10_10") (pintype "passive"))
    )
    (net (code "351") (name "~{IMU_CS}") (class "Default")
      (node (ref "J8") (pin "03") (pinfunction "03_03") (pintype "passive"))
    )
    (net (code "352") (name "~{IMU_RST}") (class "Default")
      (node (ref "J8") (pin "01") (pinfunction "01_01") (pintype "passive"))
    )
    (net (code "353") (name "~{ISO_CS}") (class "Default")
      (node (ref "J8") (pin "28") (pinfunction "28_28") (pintype "passive"))
    )
    (net (code "354") (name "~{THERMOCOUPLE_CS}") (class "Default")
      (node (ref "J8") (pin "36") (pinfunction "36_36") (pintype "passive"))
    )
  )
)
